# mcat-4cu-b-v2d.net
KiCad netlist of a schematic drawn in EAGLE
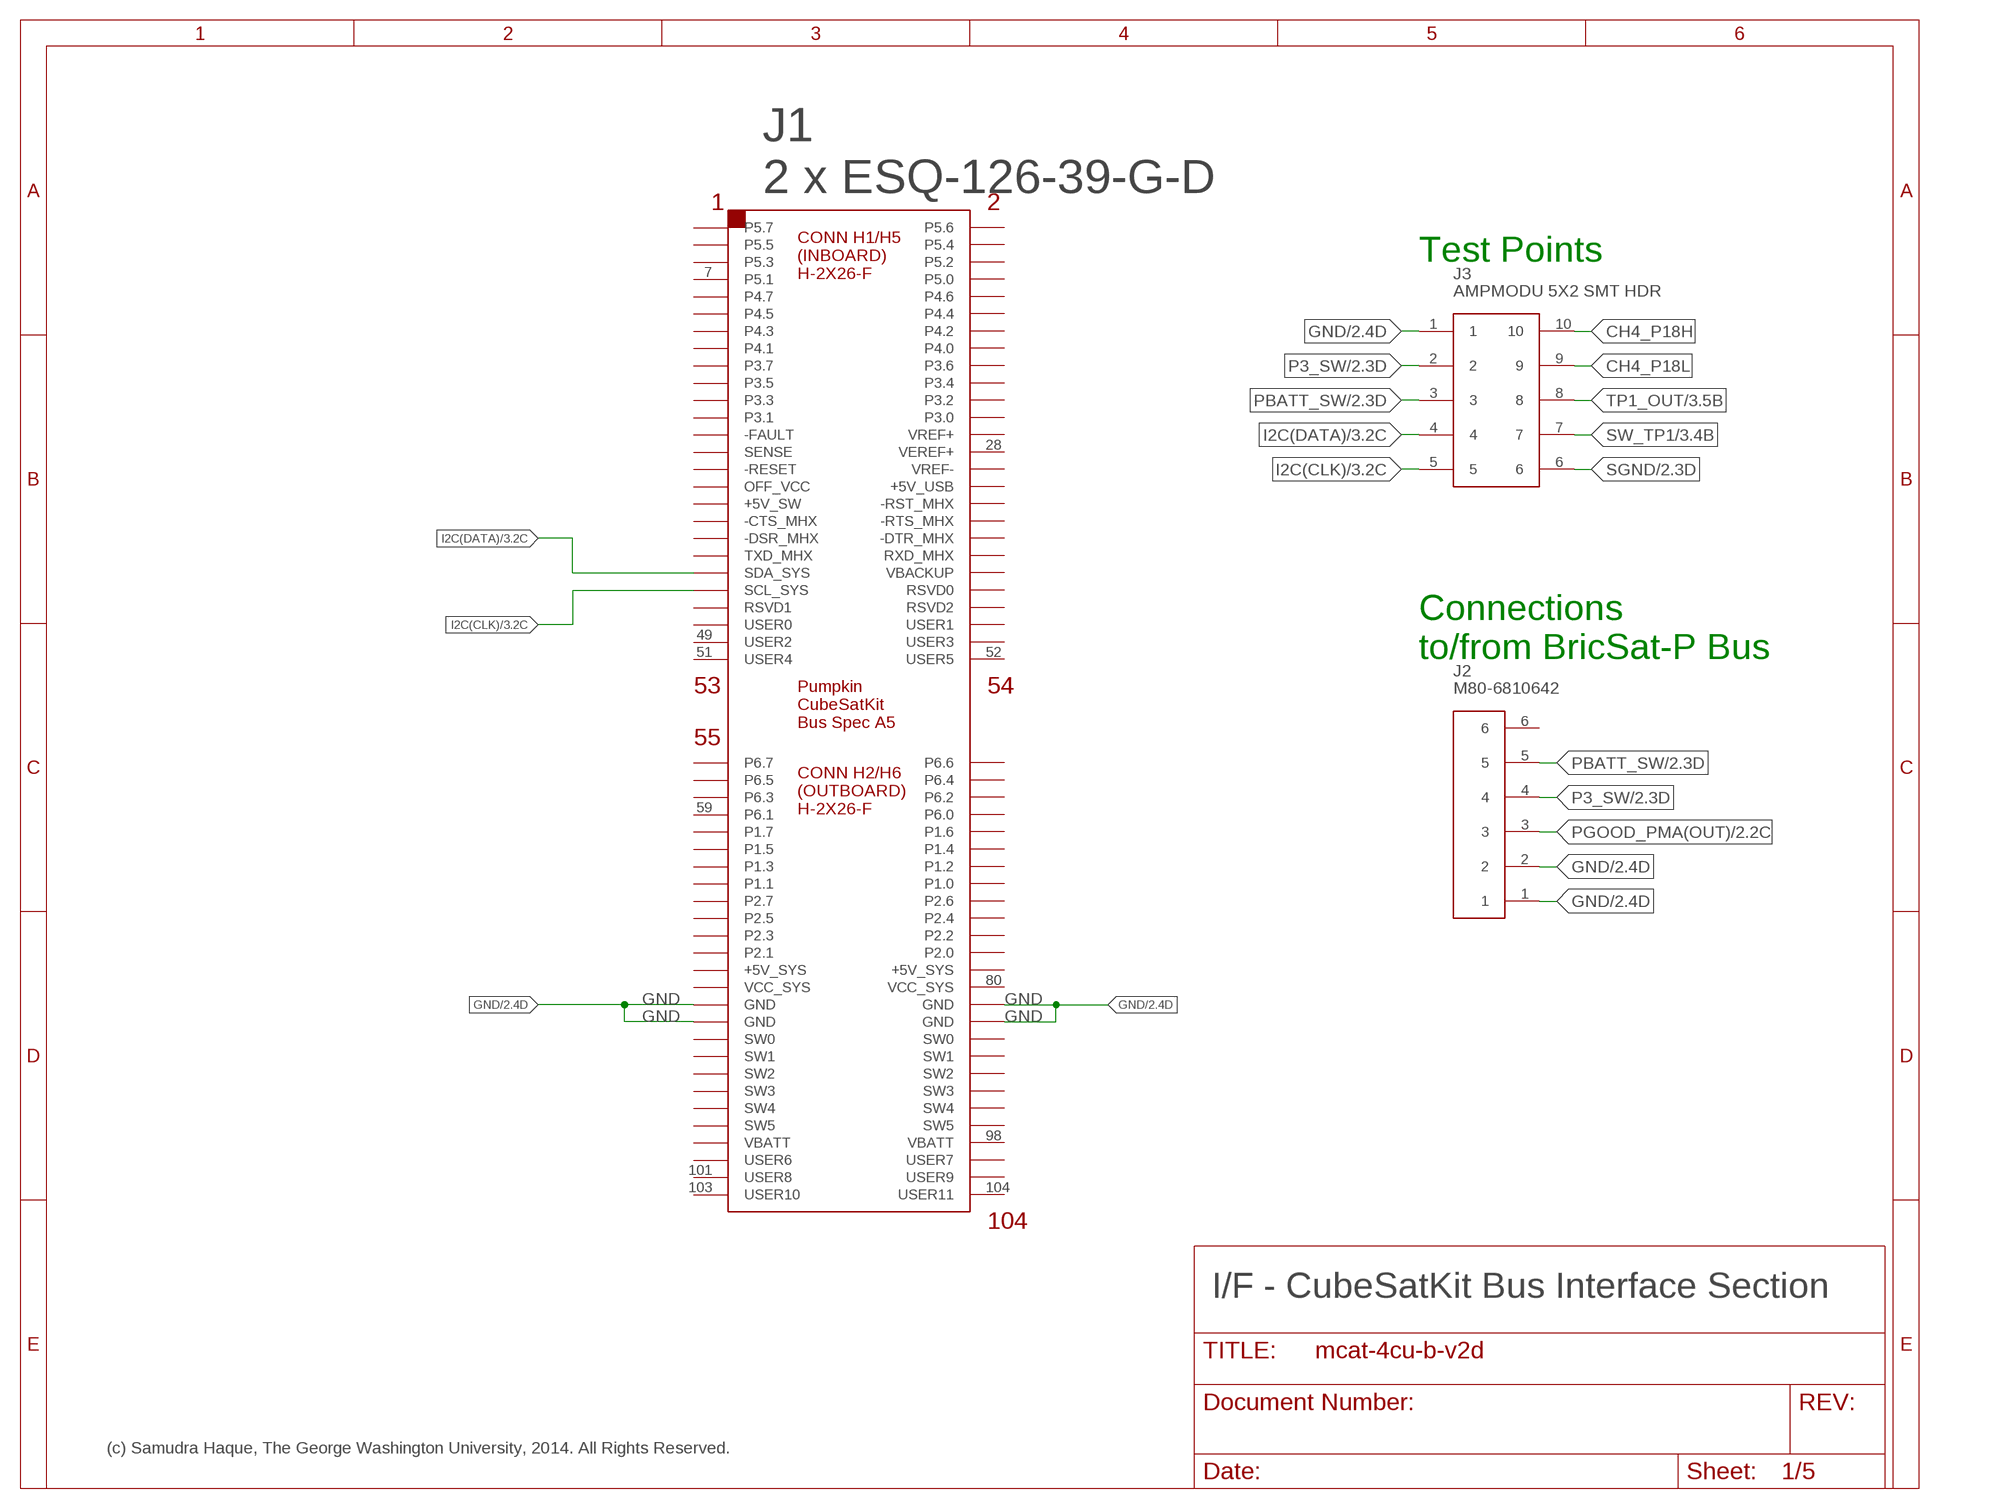
[diagram p0: schematic, sheet 1]
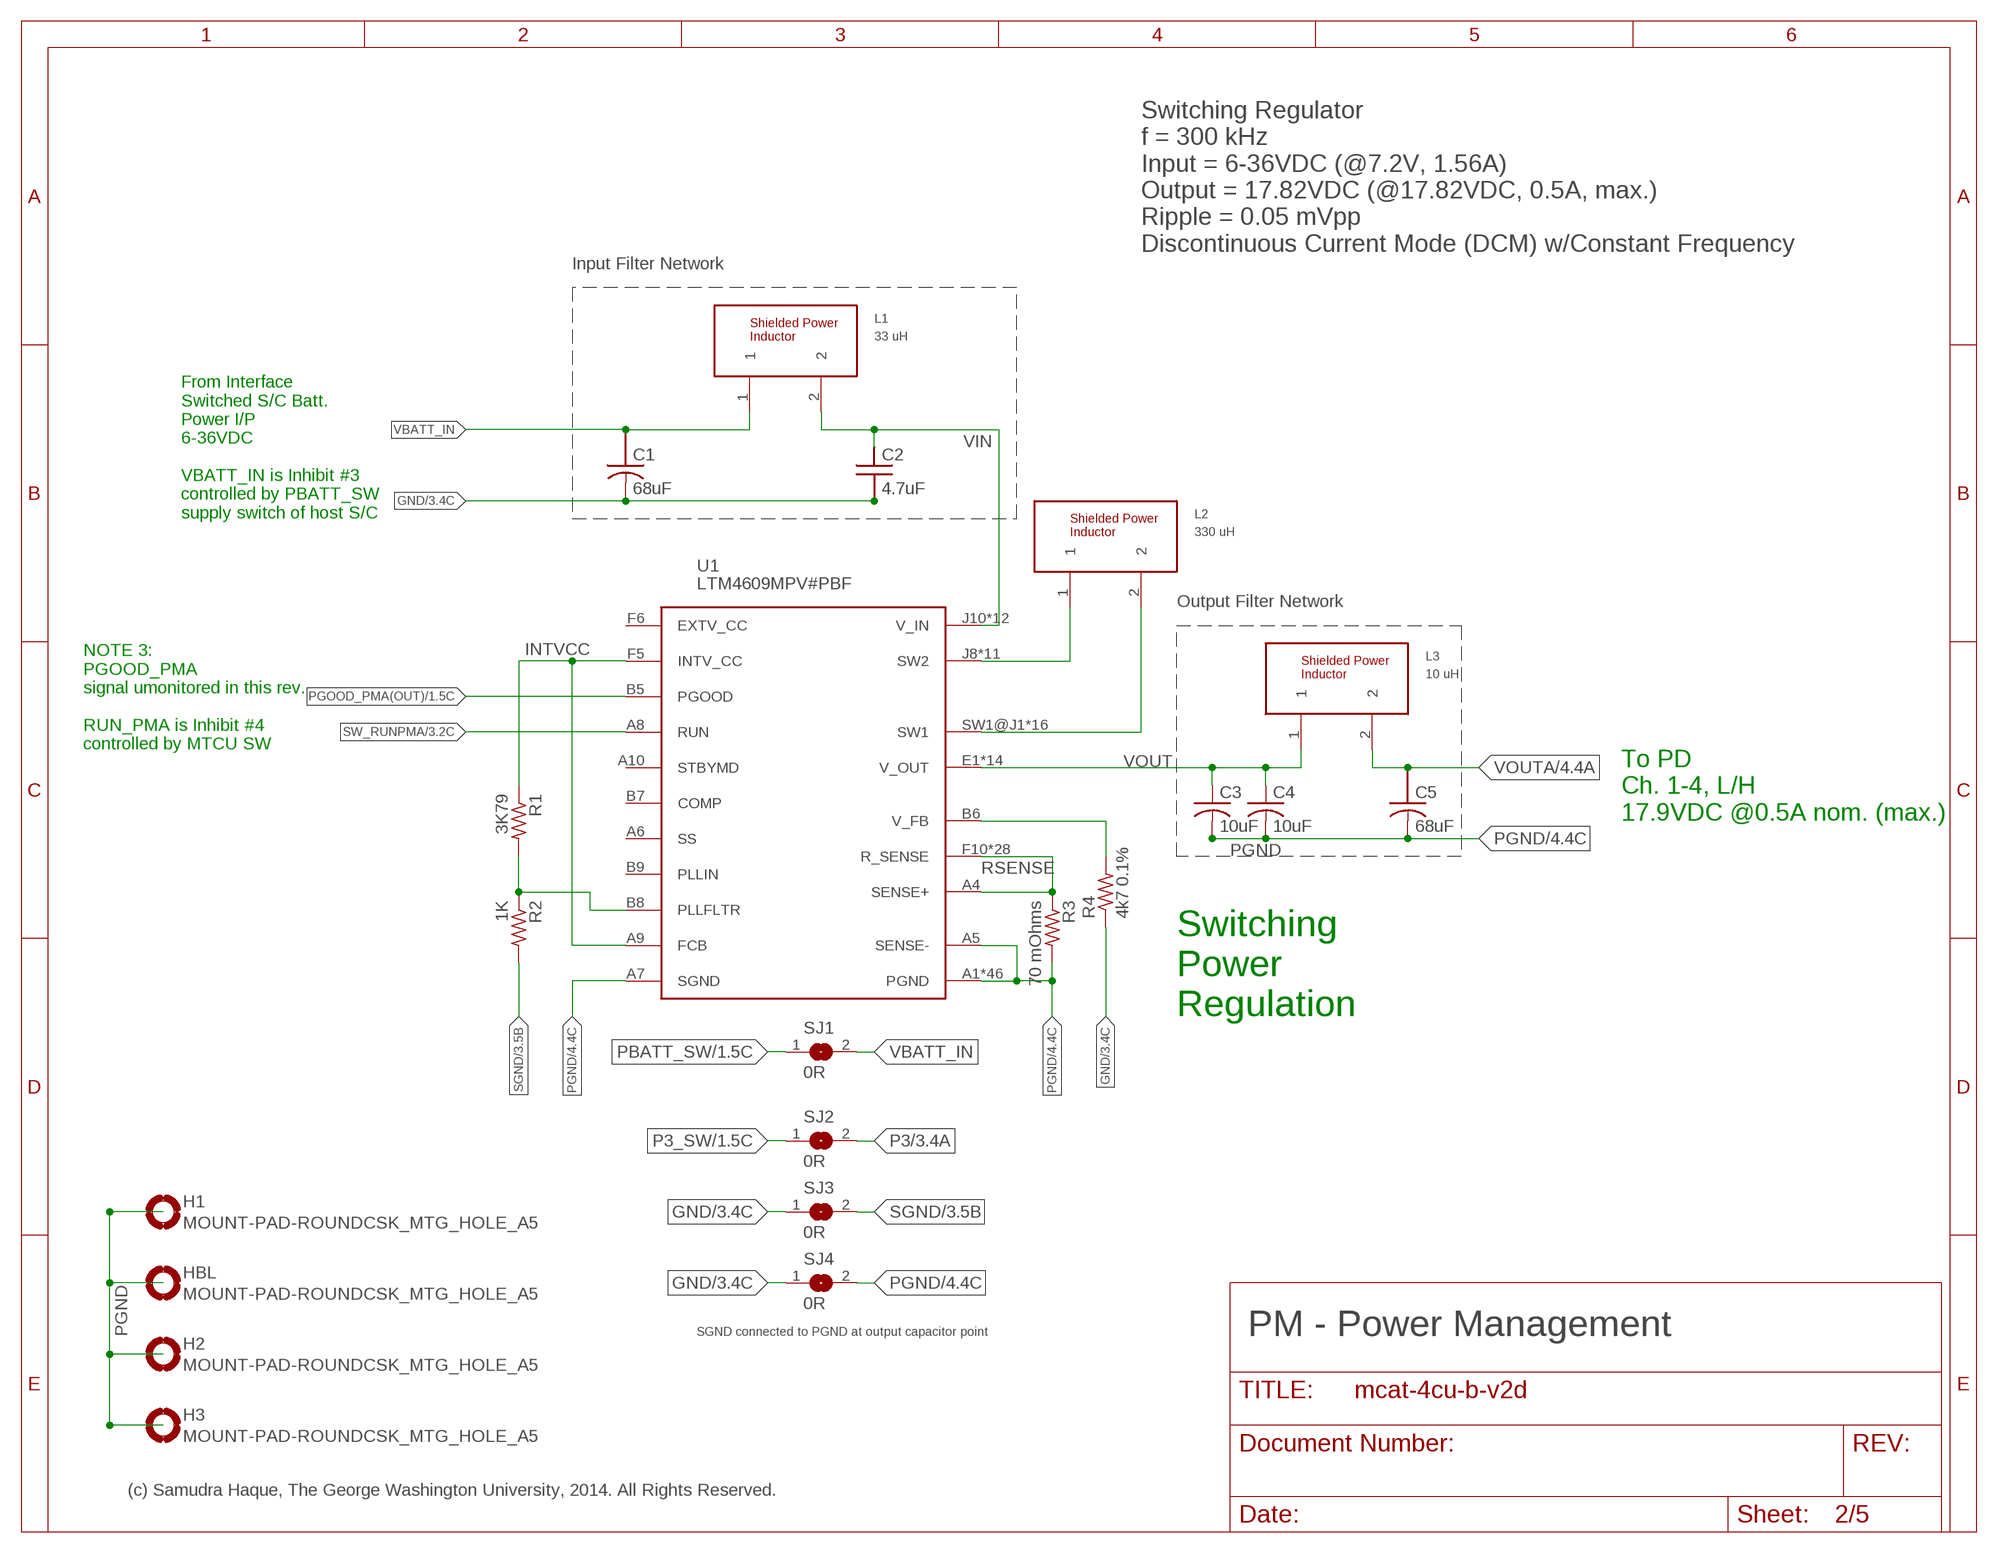
[diagram p1: schematic, sheet 2]
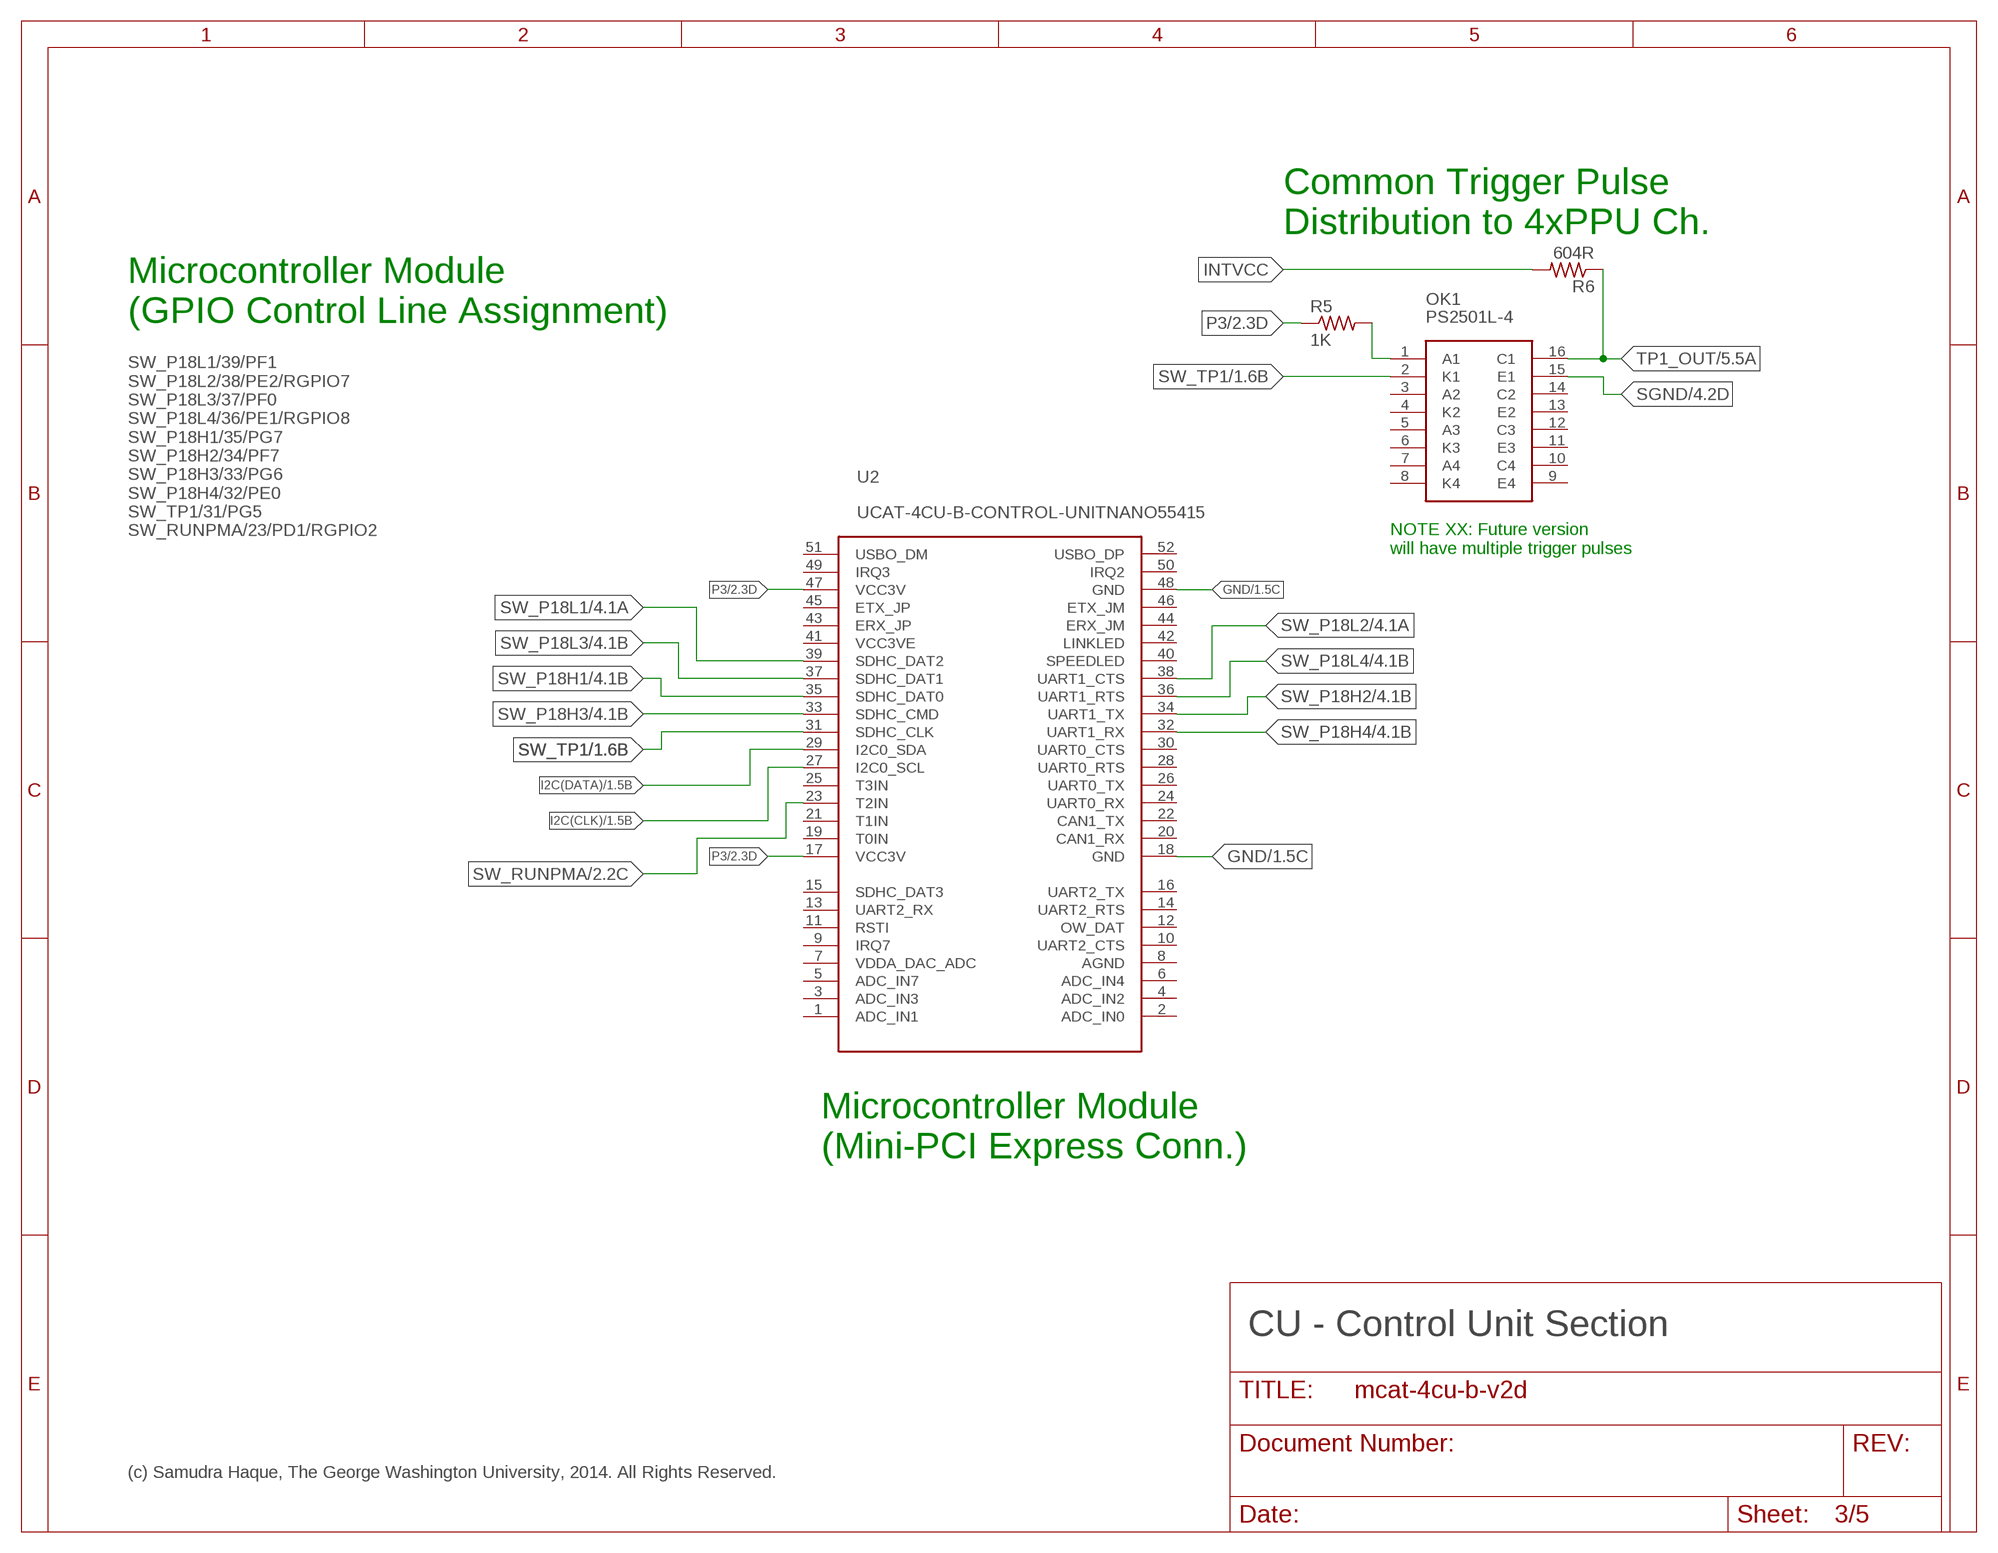
[diagram p2: schematic, sheet 3]
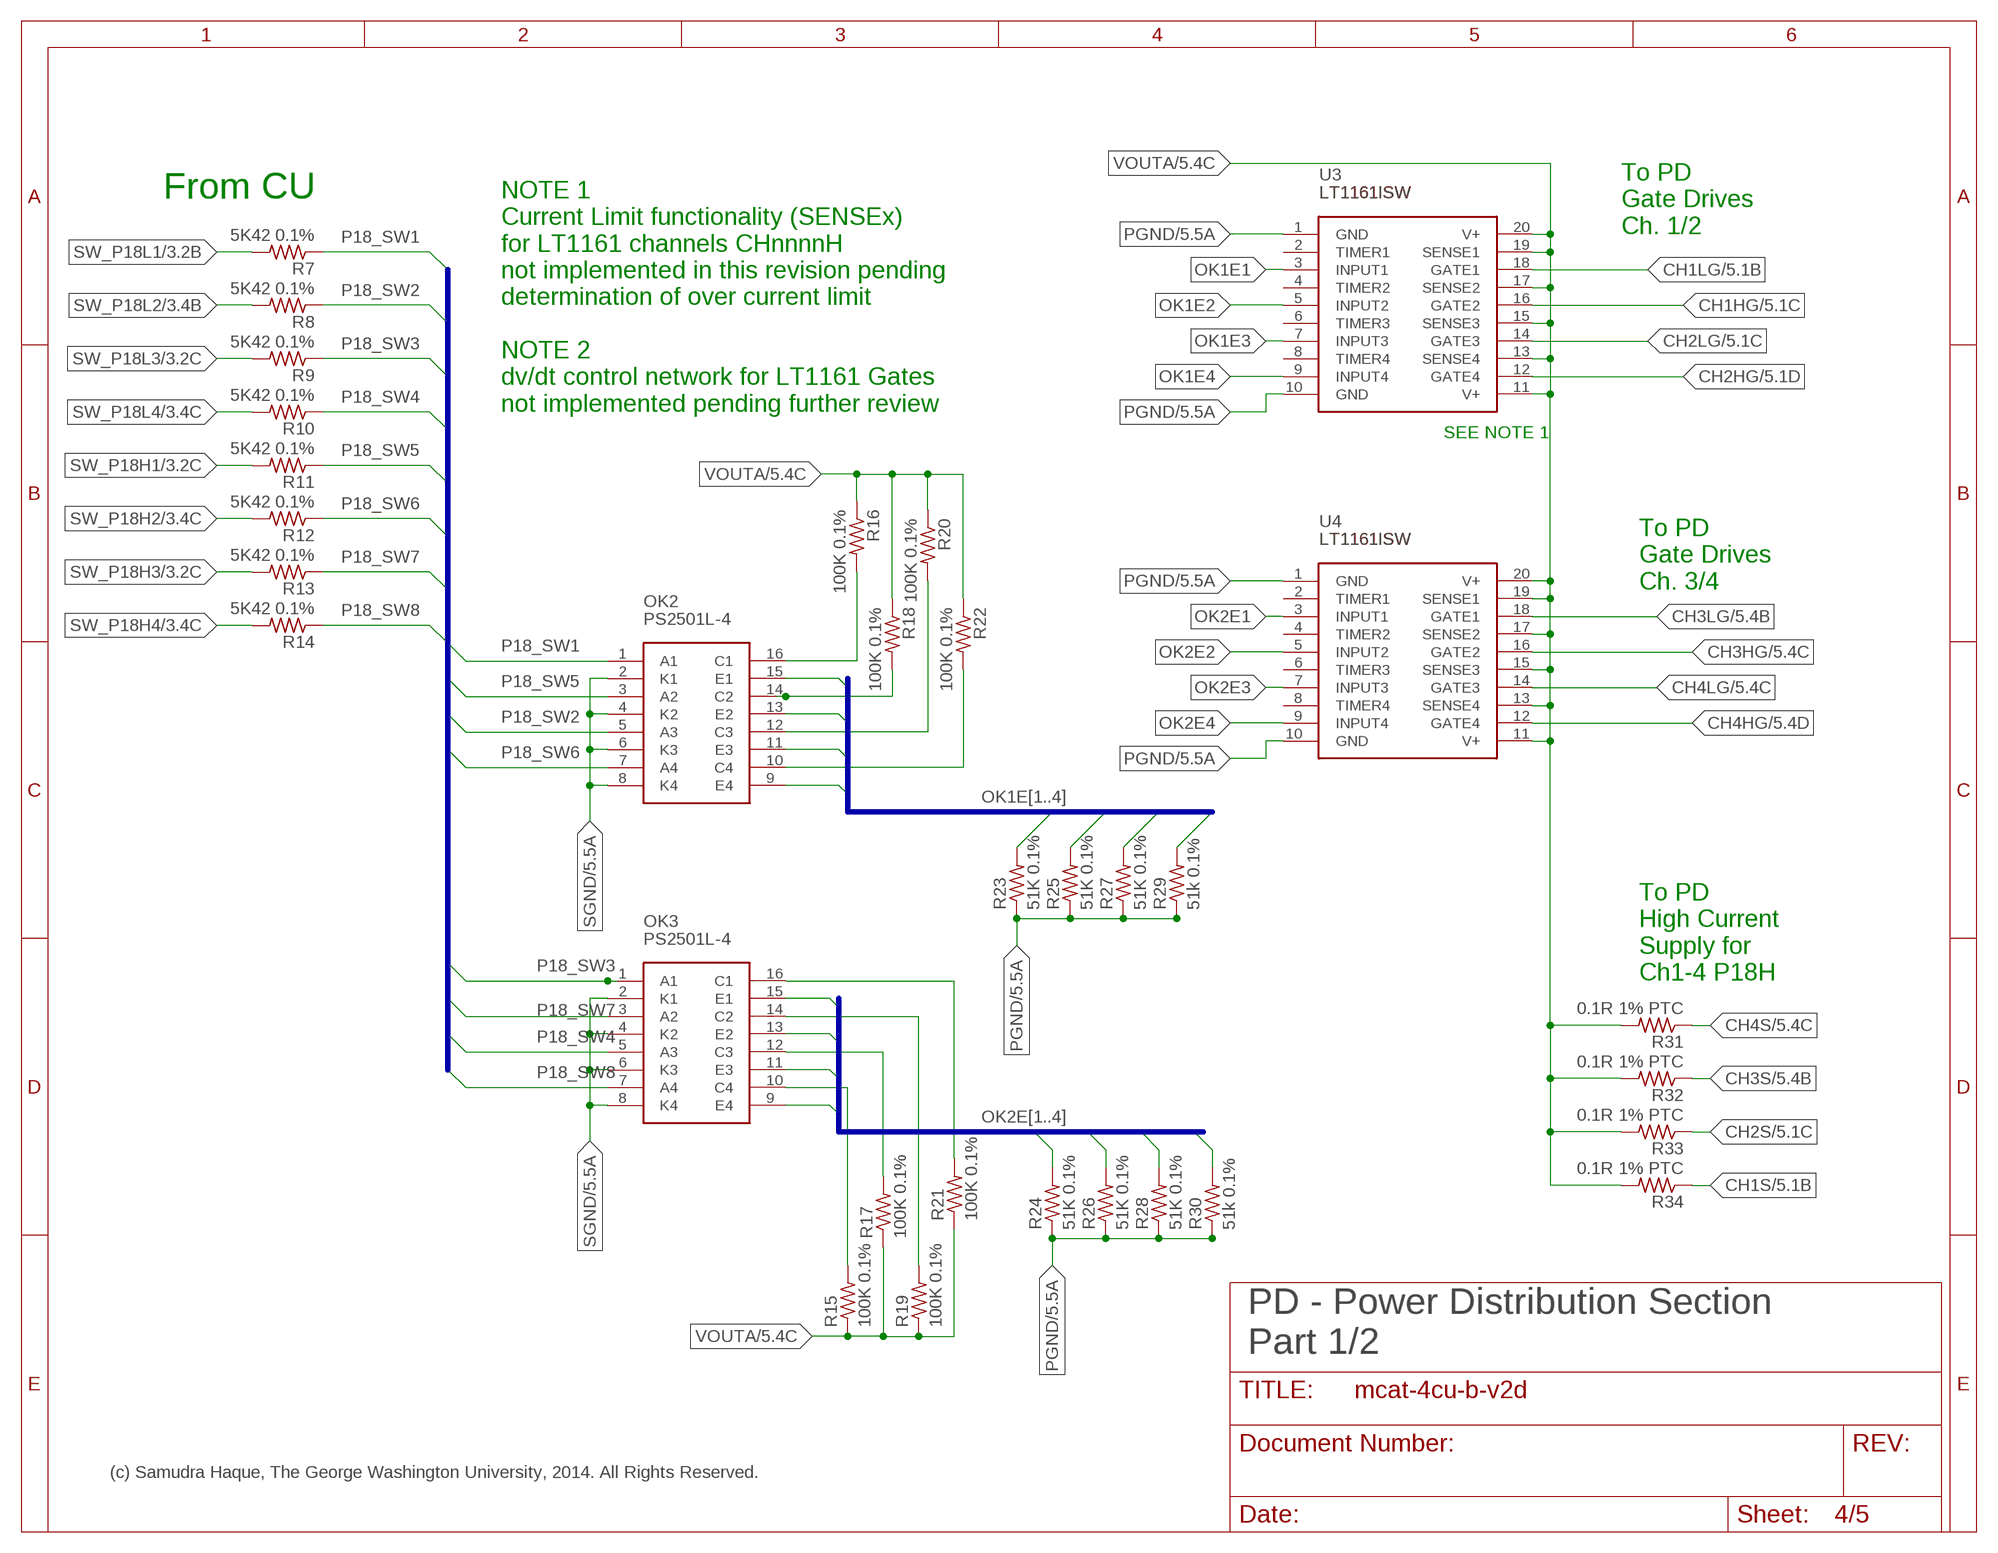
[diagram p3: schematic, sheet 4]
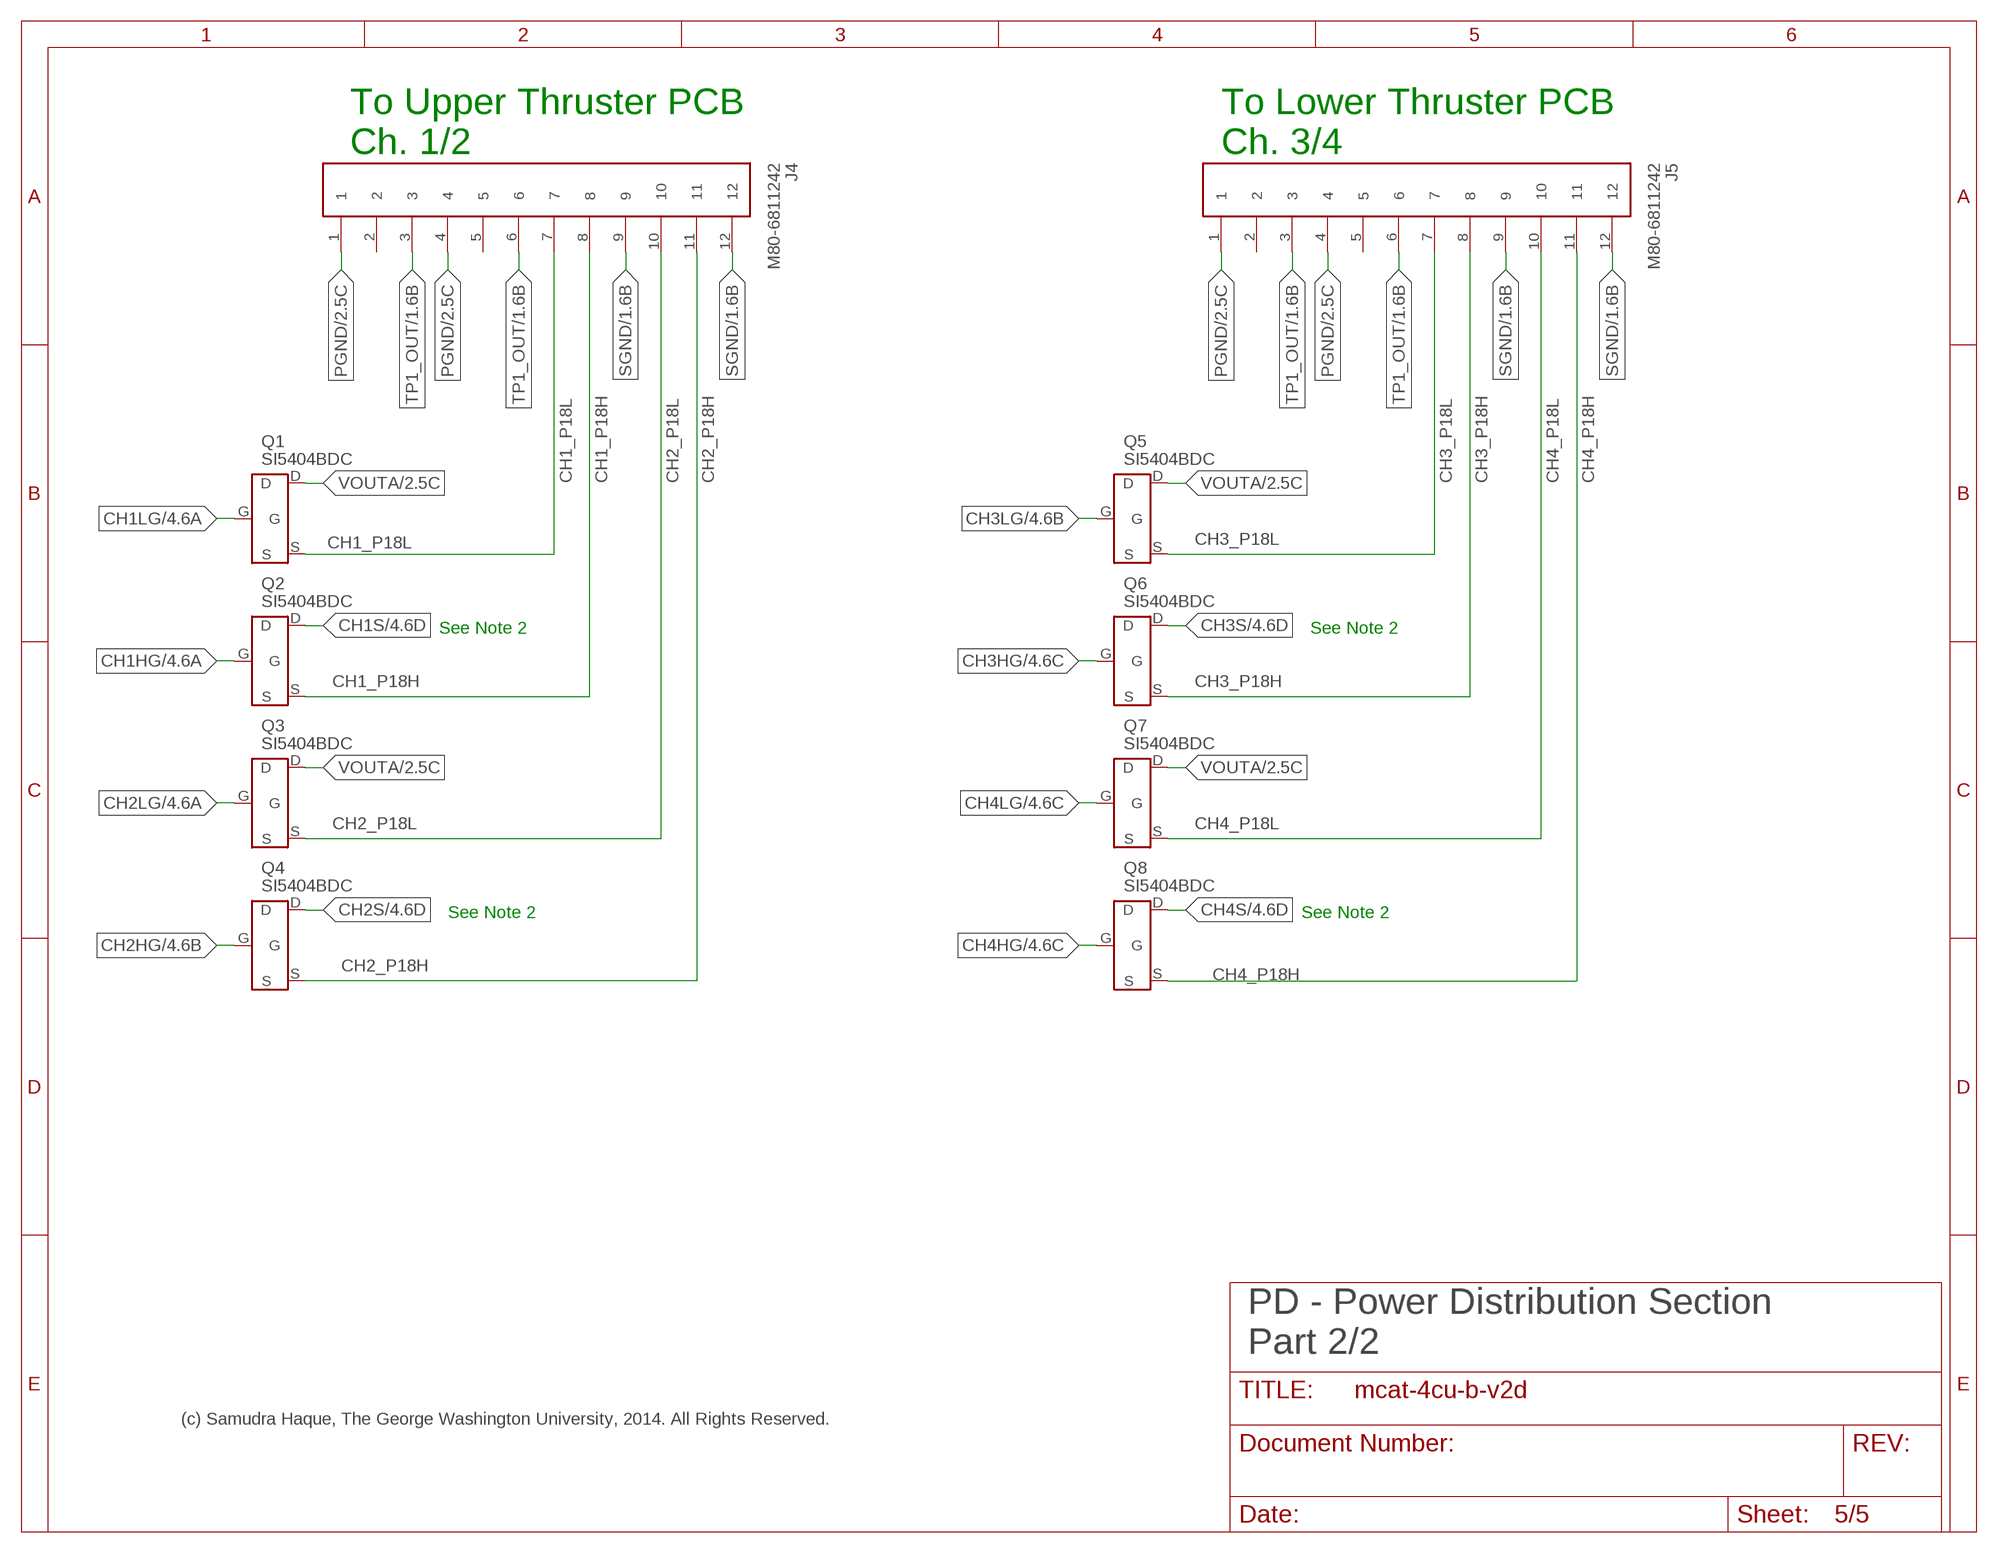
[diagram p4: schematic, sheet 5]

(export (version "E")
  (design (tool "Eeschema 10.0.6"))
  (components
    (comp (ref "OK1")
      (value "PS2501L-4")
      (footprint "eagle-import:PS2501L-4")
      (libsource (lib "eagle-import") (part "PS2501L-4"))
    )
    (comp (ref "R5")
      (value "1K")
      (footprint "eagle-import:R0805")
      (libsource (lib "eagle-import") (part "resistor_R-US_R0805"))
    )
    (comp (ref "R6")
      (value "604R")
      (footprint "eagle-import:R0805")
      (libsource (lib "eagle-import") (part "resistor_R-US_R0805"))
    )
    (comp (ref "U2")
      (value "UCAT-4CU-B-CONTROL-UNITNANO55415")
      (footprint "eagle-import:MOLEX-MINI-PCI-EXPRESS-8MM-52CKT")
      (libsource (lib "eagle-import") (part "UCAT-4CU-B-CONTROL-UNITNANO55415"))
    )
    (comp (ref "J4")
      (value "M80-6811242")
      (footprint "eagle-import:M80-68112")
      (libsource (lib "eagle-import") (part "M80-6811242"))
    )
    (comp (ref "J5")
      (value "M80-6811242")
      (footprint "eagle-import:M80-68112")
      (libsource (lib "eagle-import") (part "M80-6811242"))
    )
    (comp (ref "Q1")
      (value "SI5404BDC")
      (footprint "eagle-import:1206-8-CHIPFET")
      (libsource (lib "eagle-import") (part "SI5404BDC"))
    )
    (comp (ref "Q2")
      (value "SI5404BDC")
      (footprint "eagle-import:1206-8-CHIPFET")
      (libsource (lib "eagle-import") (part "SI5404BDC"))
    )
    (comp (ref "Q3")
      (value "SI5404BDC")
      (footprint "eagle-import:1206-8-CHIPFET")
      (libsource (lib "eagle-import") (part "SI5404BDC"))
    )
    (comp (ref "Q4")
      (value "SI5404BDC")
      (footprint "eagle-import:1206-8-CHIPFET")
      (libsource (lib "eagle-import") (part "SI5404BDC"))
    )
    (comp (ref "Q5")
      (value "SI5404BDC")
      (footprint "eagle-import:1206-8-CHIPFET")
      (libsource (lib "eagle-import") (part "SI5404BDC"))
    )
    (comp (ref "Q6")
      (value "SI5404BDC")
      (footprint "eagle-import:1206-8-CHIPFET")
      (libsource (lib "eagle-import") (part "SI5404BDC"))
    )
    (comp (ref "Q7")
      (value "SI5404BDC")
      (footprint "eagle-import:1206-8-CHIPFET")
      (libsource (lib "eagle-import") (part "SI5404BDC"))
    )
    (comp (ref "Q8")
      (value "SI5404BDC")
      (footprint "eagle-import:1206-8-CHIPFET")
      (libsource (lib "eagle-import") (part "SI5404BDC"))
    )
    (comp (ref "OK2")
      (value "PS2501L-4")
      (footprint "eagle-import:PS2501L-4")
      (libsource (lib "eagle-import") (part "PS2501L-4"))
    )
    (comp (ref "OK3")
      (value "PS2501L-4")
      (footprint "eagle-import:PS2501L-4")
      (libsource (lib "eagle-import") (part "PS2501L-4"))
    )
    (comp (ref "R7")
      (value "5K42 0.1%")
      (footprint "eagle-import:R1206")
      (libsource (lib "eagle-import") (part "resistor_R-US_R1206"))
    )
    (comp (ref "R8")
      (value "5K42 0.1%")
      (footprint "eagle-import:R1206")
      (libsource (lib "eagle-import") (part "resistor_R-US_R1206"))
    )
    (comp (ref "R9")
      (value "5K42 0.1%")
      (footprint "eagle-import:R1206")
      (libsource (lib "eagle-import") (part "resistor_R-US_R1206"))
    )
    (comp (ref "R10")
      (value "5K42 0.1%")
      (footprint "eagle-import:R1206")
      (libsource (lib "eagle-import") (part "resistor_R-US_R1206"))
    )
    (comp (ref "R11")
      (value "5K42 0.1%")
      (footprint "eagle-import:R1206")
      (libsource (lib "eagle-import") (part "resistor_R-US_R1206"))
    )
    (comp (ref "R12")
      (value "5K42 0.1%")
      (footprint "eagle-import:R1206")
      (libsource (lib "eagle-import") (part "resistor_R-US_R1206"))
    )
    (comp (ref "R13")
      (value "5K42 0.1%")
      (footprint "eagle-import:R1206")
      (libsource (lib "eagle-import") (part "resistor_R-US_R1206"))
    )
    (comp (ref "R14")
      (value "5K42 0.1%")
      (footprint "eagle-import:R1206")
      (libsource (lib "eagle-import") (part "resistor_R-US_R1206"))
    )
    (comp (ref "R15")
      (value "100K 0.1%")
      (footprint "eagle-import:R0402")
      (libsource (lib "eagle-import") (part "resistor_R-US_R0402"))
    )
    (comp (ref "R16")
      (value "100K 0.1%")
      (footprint "eagle-import:R0402")
      (libsource (lib "eagle-import") (part "resistor_R-US_R0402"))
    )
    (comp (ref "R17")
      (value "100K 0.1%")
      (footprint "eagle-import:R0402")
      (libsource (lib "eagle-import") (part "resistor_R-US_R0402"))
    )
    (comp (ref "R18")
      (value "100K 0.1%")
      (footprint "eagle-import:R0402")
      (libsource (lib "eagle-import") (part "resistor_R-US_R0402"))
    )
    (comp (ref "R19")
      (value "100K 0.1%")
      (footprint "eagle-import:R0402")
      (libsource (lib "eagle-import") (part "resistor_R-US_R0402"))
    )
    (comp (ref "R20")
      (value "100K 0.1%")
      (footprint "eagle-import:R0402")
      (libsource (lib "eagle-import") (part "resistor_R-US_R0402"))
    )
    (comp (ref "R21")
      (value "100K 0.1%")
      (footprint "eagle-import:R0402")
      (libsource (lib "eagle-import") (part "resistor_R-US_R0402"))
    )
    (comp (ref "R22")
      (value "100K 0.1%")
      (footprint "eagle-import:R0402")
      (libsource (lib "eagle-import") (part "resistor_R-US_R0402"))
    )
    (comp (ref "R23")
      (value "51K 0.1%")
      (footprint "eagle-import:R0603")
      (libsource (lib "eagle-import") (part "resistor_R-US_R0603"))
    )
    (comp (ref "R24")
      (value "51K 0.1%")
      (footprint "eagle-import:R0603")
      (libsource (lib "eagle-import") (part "resistor_R-US_R0603"))
    )
    (comp (ref "R25")
      (value "51K 0.1%")
      (footprint "eagle-import:R0603")
      (libsource (lib "eagle-import") (part "resistor_R-US_R0603"))
    )
    (comp (ref "R26")
      (value "51K 0.1%")
      (footprint "eagle-import:R0603")
      (libsource (lib "eagle-import") (part "resistor_R-US_R0603"))
    )
    (comp (ref "R27")
      (value "51K 0.1%")
      (footprint "eagle-import:R0603")
      (libsource (lib "eagle-import") (part "resistor_R-US_R0603"))
    )
    (comp (ref "R28")
      (value "51K 0.1%")
      (footprint "eagle-import:R0603")
      (libsource (lib "eagle-import") (part "resistor_R-US_R0603"))
    )
    (comp (ref "R29")
      (value "51k 0.1%")
      (footprint "eagle-import:R0603")
      (libsource (lib "eagle-import") (part "resistor_R-US_R0603"))
    )
    (comp (ref "R30")
      (value "51k 0.1%")
      (footprint "eagle-import:R0603")
      (libsource (lib "eagle-import") (part "resistor_R-US_R0603"))
    )
    (comp (ref "R31")
      (value "0.1R 1% PTC")
      (footprint "eagle-import:R0402")
      (libsource (lib "eagle-import") (part "R-US_R0402"))
    )
    (comp (ref "R32")
      (value "0.1R 1% PTC")
      (footprint "eagle-import:R0402")
      (libsource (lib "eagle-import") (part "R-US_R0402"))
    )
    (comp (ref "R33")
      (value "0.1R 1% PTC")
      (footprint "eagle-import:R0402")
      (libsource (lib "eagle-import") (part "R-US_R0402"))
    )
    (comp (ref "R34")
      (value "0.1R 1% PTC")
      (footprint "eagle-import:R0402")
      (libsource (lib "eagle-import") (part "R-US_R0402"))
    )
    (comp (ref "U3")
      (value "LT1161ISW")
      (footprint "eagle-import:20-LEAD-PLASTIC-SO")
      (libsource (lib "eagle-import") (part "LT1161ISW"))
    )
    (comp (ref "U4")
      (value "LT1161ISW")
      (footprint "eagle-import:20-LEAD-PLASTIC-SO")
      (libsource (lib "eagle-import") (part "LT1161ISW"))
    )
    (comp (ref "C1")
      (value "68uF")
      (footprint "eagle-import:OS-CON-SVPF-F12")
      (libsource (lib "eagle-import") (part "OSCON-50SVPF68M"))
    )
    (comp (ref "C2")
      (value "4.7uF")
      (footprint "eagle-import:MLCC-X7R-1210")
      (libsource (lib "eagle-import") (part "AVX-LD105C475KAB2A"))
    )
    (comp (ref "C3")
      (value "10uF")
      (footprint "eagle-import:C1210K")
      (libsource (lib "eagle-import") (part "C-USC1210K"))
    )
    (comp (ref "C4")
      (value "10uF")
      (footprint "eagle-import:C1210K")
      (libsource (lib "eagle-import") (part "C-USC1210K"))
    )
    (comp (ref "C5")
      (value "68uF")
      (footprint "eagle-import:OS-CON-SVPF-F12")
      (libsource (lib "eagle-import") (part "OSCON-50SVPF68M"))
    )
    (comp (ref "H1")
      (value "MOUNT-PAD-ROUNDCSK_MTG_HOLE_A5")
      (footprint "eagle-import:CSK_MOUNTING_HOLE")
      (libsource (lib "eagle-import") (part "MOUNT-PAD-ROUNDCSK_MTG_HOLE_A5"))
    )
    (comp (ref "H2")
      (value "MOUNT-PAD-ROUNDCSK_MTG_HOLE_A5")
      (footprint "eagle-import:CSK_MOUNTING_HOLE")
      (libsource (lib "eagle-import") (part "MOUNT-PAD-ROUNDCSK_MTG_HOLE_A5"))
    )
    (comp (ref "H3")
      (value "MOUNT-PAD-ROUNDCSK_MTG_HOLE_A5")
      (footprint "eagle-import:CSK_MOUNTING_HOLE")
      (libsource (lib "eagle-import") (part "MOUNT-PAD-ROUNDCSK_MTG_HOLE_A5"))
    )
    (comp (ref "HBL")
      (value "MOUNT-PAD-ROUNDCSK_MTG_HOLE_A5")
      (footprint "eagle-import:CSK_MOUNTING_HOLE")
      (libsource (lib "eagle-import") (part "MOUNT-PAD-ROUNDCSK_MTG_HOLE_A5"))
    )
    (comp (ref "L1")
      (value "33 uH")
      (footprint "eagle-import:MSS1048")
      (libsource (lib "eagle-import") (part "MSS1038-333ML_"))
    )
    (comp (ref "L2")
      (value "330 uH")
      (footprint "eagle-import:MSS1048")
      (libsource (lib "eagle-import") (part "MSS1048-334KL_"))
    )
    (comp (ref "L3")
      (value "10 uH")
      (footprint "eagle-import:SERIES-POWER-INDUCTORS")
      (fields (field (name "MF") "PANASONIC") (field (name "MPN") "ELL5PS100M"))
      (libsource (lib "eagle-import") (part "ELL-5PS100M"))
    )
    (comp (ref "R1")
      (value "3K79")
      (footprint "eagle-import:R0805")
      (libsource (lib "eagle-import") (part "R-US_R0805"))
    )
    (comp (ref "R2")
      (value "1K")
      (footprint "eagle-import:R0805")
      (libsource (lib "eagle-import") (part "R-US_R0805"))
    )
    (comp (ref "R3")
      (value "70 mOhms")
      (footprint "eagle-import:R1206")
      (libsource (lib "eagle-import") (part "resistor_R-US_R1206"))
    )
    (comp (ref "R4")
      (value "4k7 0.1%")
      (footprint "eagle-import:R0603")
      (libsource (lib "eagle-import") (part "resistor_R-US_R0603"))
    )
    (comp (ref "SJ1") (value "0R") (footprint "eagle-import:SJ") (libsource (lib "eagle-import") (part "SJ")))
    (comp (ref "SJ2") (value "0R") (footprint "eagle-import:SJ") (libsource (lib "eagle-import") (part "SJ")))
    (comp (ref "SJ3") (value "0R") (footprint "eagle-import:SJ") (libsource (lib "eagle-import") (part "SJ")))
    (comp (ref "SJ4") (value "0R") (footprint "eagle-import:SJ") (libsource (lib "eagle-import") (part "SJ")))
    (comp (ref "U1")
      (value "LTM4609MPV#PBF")
      (footprint "eagle-import:LGA-141-LTC-05-08-1840-B")
      (libsource (lib "eagle-import") (part "LTM4609MPV#PBFROHS/HITEMP"))
    )
    (comp (ref "J1")
      (value "2 x ESQ-126-39-G-D")
      (footprint "eagle-import:CSK-BUS-PKG")
      (libsource (lib "eagle-import") (part "CSK-BUS-CONN2X2X26"))
    )
    (comp (ref "J2")
      (value "M80-6810642")
      (footprint "eagle-import:M80-68106")
      (libsource (lib "eagle-import") (part "M80-6810642"))
    )
    (comp (ref "J3")
      (value "AMPMODU 5X2 SMT HDR")
      (footprint "eagle-import:AMPMODU-SMT-PIN-HEADER-5X2")
      (libsource (lib "eagle-import") (part "AMPMODU-5-146131-X(5X2)"))
    )
  )
  (nets
    (net (code "3") (name "CH1HG") (class "Default")
      (node (ref "Q2") (pin "G") (pinfunction "G_G") (pintype "bidirectional"))
      (node (ref "U3") (pin "16") (pinfunction "GATE2_16") (pintype "bidirectional"))
    )
    (net (code "4") (name "CH1LG") (class "Default")
      (node (ref "Q1") (pin "G") (pinfunction "G_G") (pintype "bidirectional"))
      (node (ref "U3") (pin "18") (pinfunction "GATE1_18") (pintype "bidirectional"))
    )
    (net (code "5") (name "CH1S") (class "Default")
      (node (ref "Q2") (pin "D") (pinfunction "D_D") (pintype "bidirectional"))
      (node (ref "R34") (pin "1") (pinfunction "1_1") (pintype "passive"))
    )
    (net (code "6") (name "CH1_P18H") (class "Default")
      (node (ref "J4") (pin "8") (pinfunction "8_8") (pintype "bidirectional"))
      (node (ref "Q2") (pin "S") (pinfunction "S_S") (pintype "bidirectional"))
    )
    (net (code "7") (name "CH1_P18L") (class "Default")
      (node (ref "J4") (pin "7") (pinfunction "7_7") (pintype "bidirectional"))
      (node (ref "Q1") (pin "S") (pinfunction "S_S") (pintype "bidirectional"))
    )
    (net (code "8") (name "CH2HG") (class "Default")
      (node (ref "Q4") (pin "G") (pinfunction "G_G") (pintype "bidirectional"))
      (node (ref "U3") (pin "12") (pinfunction "GATE4_12") (pintype "bidirectional"))
    )
    (net (code "9") (name "CH2LG") (class "Default")
      (node (ref "Q3") (pin "G") (pinfunction "G_G") (pintype "bidirectional"))
      (node (ref "U3") (pin "14") (pinfunction "GATE3_14") (pintype "bidirectional"))
    )
    (net (code "10") (name "CH2S") (class "Default")
      (node (ref "Q4") (pin "D") (pinfunction "D_D") (pintype "bidirectional"))
      (node (ref "R33") (pin "1") (pinfunction "1_1") (pintype "passive"))
    )
    (net (code "11") (name "CH2_P18H") (class "Default")
      (node (ref "J4") (pin "11") (pinfunction "11_11") (pintype "bidirectional"))
      (node (ref "Q4") (pin "S") (pinfunction "S_S") (pintype "bidirectional"))
    )
    (net (code "12") (name "CH2_P18L") (class "Default")
      (node (ref "J4") (pin "10") (pinfunction "10_10") (pintype "bidirectional"))
      (node (ref "Q3") (pin "S") (pinfunction "S_S") (pintype "bidirectional"))
    )
    (net (code "13") (name "CH3HG") (class "Default")
      (node (ref "Q6") (pin "G") (pinfunction "G_G") (pintype "bidirectional"))
      (node (ref "U4") (pin "16") (pinfunction "GATE2_16") (pintype "bidirectional"))
    )
    (net (code "14") (name "CH3LG") (class "Default")
      (node (ref "Q5") (pin "G") (pinfunction "G_G") (pintype "bidirectional"))
      (node (ref "U4") (pin "18") (pinfunction "GATE1_18") (pintype "bidirectional"))
    )
    (net (code "15") (name "CH3S") (class "Default")
      (node (ref "Q6") (pin "D") (pinfunction "D_D") (pintype "bidirectional"))
      (node (ref "R32") (pin "1") (pinfunction "1_1") (pintype "passive"))
    )
    (net (code "16") (name "CH3_P18H") (class "Default")
      (node (ref "J5") (pin "8") (pinfunction "8_8") (pintype "bidirectional"))
      (node (ref "Q6") (pin "S") (pinfunction "S_S") (pintype "bidirectional"))
    )
    (net (code "17") (name "CH3_P18L") (class "Default")
      (node (ref "J5") (pin "7") (pinfunction "7_7") (pintype "bidirectional"))
      (node (ref "Q5") (pin "S") (pinfunction "S_S") (pintype "bidirectional"))
    )
    (net (code "18") (name "CH4HG") (class "Default")
      (node (ref "Q8") (pin "G") (pinfunction "G_G") (pintype "bidirectional"))
      (node (ref "U4") (pin "12") (pinfunction "GATE4_12") (pintype "bidirectional"))
    )
    (net (code "19") (name "CH4LG") (class "Default")
      (node (ref "Q7") (pin "G") (pinfunction "G_G") (pintype "bidirectional"))
      (node (ref "U4") (pin "14") (pinfunction "GATE3_14") (pintype "bidirectional"))
    )
    (net (code "20") (name "CH4S") (class "Default")
      (node (ref "Q8") (pin "D") (pinfunction "D_D") (pintype "bidirectional"))
      (node (ref "R31") (pin "1") (pinfunction "1_1") (pintype "passive"))
    )
    (net (code "21") (name "CH4_P18H") (class "Default")
      (node (ref "J3") (pin "10") (pinfunction "10_10") (pintype "bidirectional"))
      (node (ref "J5") (pin "11") (pinfunction "11_11") (pintype "bidirectional"))
      (node (ref "Q8") (pin "S") (pinfunction "S_S") (pintype "bidirectional"))
    )
    (net (code "22") (name "CH4_P18L") (class "Default")
      (node (ref "J3") (pin "9") (pinfunction "9_9") (pintype "bidirectional"))
      (node (ref "J5") (pin "10") (pinfunction "10_10") (pintype "bidirectional"))
      (node (ref "Q7") (pin "S") (pinfunction "S_S") (pintype "bidirectional"))
    )
    (net (code "23") (name "GND") (class "Default")
      (node (ref "C1") (pin "K1") (pinfunction "K_K1") (pintype "passive"))
      (node (ref "C2") (pin "2") (pinfunction "2_2") (pintype "passive"))
      (node (ref "J1") (pin "81") (pinfunction "GND_81") (pintype "bidirectional"))
      (node (ref "J1") (pin "82") (pinfunction "GND_82") (pintype "bidirectional"))
      (node (ref "J1") (pin "83") (pinfunction "GND_83") (pintype "bidirectional"))
      (node (ref "J1") (pin "84") (pinfunction "GND_84") (pintype "bidirectional"))
      (node (ref "J2") (pin "1") (pinfunction "1_1") (pintype "bidirectional"))
      (node (ref "J2") (pin "2") (pinfunction "2_2") (pintype "bidirectional"))
      (node (ref "J3") (pin "1") (pinfunction "1_1") (pintype "bidirectional"))
      (node (ref "R4") (pin "1") (pinfunction "1_1") (pintype "passive"))
      (node (ref "SJ3") (pin "1") (pinfunction "1_1") (pintype "passive"))
      (node (ref "SJ4") (pin "1") (pinfunction "1_1") (pintype "passive"))
      (node (ref "U2") (pin "18") (pinfunction "GND_18") (pintype "bidirectional"))
      (node (ref "U2") (pin "48") (pinfunction "GND_48") (pintype "bidirectional"))
    )
    (net (code "24") (name "I2C(CLK)") (class "Default")
      (node (ref "J1") (pin "43") (pinfunction "SCL_SYS_43") (pintype "bidirectional"))
      (node (ref "J3") (pin "5") (pinfunction "5_5") (pintype "bidirectional"))
      (node (ref "U2") (pin "27") (pinfunction "I2C0_SCL_27") (pintype "bidirectional"))
    )
    (net (code "25") (name "I2C(DATA)") (class "Default")
      (node (ref "J1") (pin "41") (pinfunction "SDA_SYS_41") (pintype "bidirectional"))
      (node (ref "J3") (pin "4") (pinfunction "4_4") (pintype "bidirectional"))
      (node (ref "U2") (pin "29") (pinfunction "I2C0_SDA_29") (pintype "bidirectional"))
    )
    (net (code "26") (name "INTVCC") (class "Default")
      (node (ref "R1") (pin "1") (pinfunction "1_1") (pintype "passive"))
      (node (ref "R6") (pin "2") (pinfunction "2_2") (pintype "passive"))
      (node (ref "U1") (pin "A9") (pinfunction "FCB_A9") (pintype "bidirectional"))
      (node (ref "U1") (pin "F5") (pinfunction "INTV_CC_F5") (pintype "bidirectional"))
    )
    (net (code "27") (name "Net-(L2-Pad1)") (class "Default")
      (node (ref "L2") (pin "1") (pinfunction "1_1") (pintype "bidirectional"))
      (node (ref "U1") (pin "J8") (pinfunction "SW2_J8") (pintype "bidirectional"))
      (node (ref "U1") (pin "J9") (pinfunction "SW2_J9") (pintype "bidirectional"))
      (node (ref "U1") (pin "K7") (pinfunction "SW2_K7") (pintype "bidirectional"))
      (node (ref "U1") (pin "K8") (pinfunction "SW2_K8") (pintype "bidirectional"))
      (node (ref "U1") (pin "K9") (pinfunction "SW2_K9") (pintype "bidirectional"))
      (node (ref "U1") (pin "L7") (pinfunction "SW2_L7") (pintype "bidirectional"))
      (node (ref "U1") (pin "L8") (pinfunction "SW2_L8") (pintype "bidirectional"))
      (node (ref "U1") (pin "L9") (pinfunction "SW2_L9") (pintype "bidirectional"))
      (node (ref "U1") (pin "M7") (pinfunction "SW2_M7") (pintype "bidirectional"))
      (node (ref "U1") (pin "M8") (pinfunction "SW2_M8") (pintype "bidirectional"))
      (node (ref "U1") (pin "M9") (pinfunction "SW2_M9") (pintype "bidirectional"))
    )
    (net (code "28") (name "Net-(L2-Pad2)") (class "Default")
      (node (ref "L2") (pin "2") (pinfunction "2_2") (pintype "bidirectional"))
      (node (ref "U1") (pin "SW1@J1") (pinfunction "SW1_SW1@J1") (pintype "bidirectional"))
      (node (ref "U1") (pin "SW1@J2") (pinfunction "SW1_SW1@J2") (pintype "bidirectional"))
      (node (ref "U1") (pin "SW1@J3") (pinfunction "SW1_SW1@J3") (pintype "bidirectional"))
      (node (ref "U1") (pin "SW1@J4") (pinfunction "SW1_SW1@J4") (pintype "bidirectional"))
      (node (ref "U1") (pin "SW1@K1") (pinfunction "SW1_SW1@K1") (pintype "bidirectional"))
      (node (ref "U1") (pin "SW1@K2") (pinfunction "SW1_SW1@K2") (pintype "bidirectional"))
      (node (ref "U1") (pin "SW1@K3") (pinfunction "SW1_SW1@K3") (pintype "bidirectional"))
      (node (ref "U1") (pin "SW1@K4") (pinfunction "SW1_SW1@K4") (pintype "bidirectional"))
      (node (ref "U1") (pin "SW1@L1") (pinfunction "SW1_SW1@L1") (pintype "bidirectional"))
      (node (ref "U1") (pin "SW1@L2") (pinfunction "SW1_SW1@L2") (pintype "bidirectional"))
      (node (ref "U1") (pin "SW1@L3") (pinfunction "SW1_SW1@L3") (pintype "bidirectional"))
      (node (ref "U1") (pin "SW1@L4") (pinfunction "SW1_SW1@L4") (pintype "bidirectional"))
      (node (ref "U1") (pin "SW1@M1") (pinfunction "SW1_SW1@M1") (pintype "bidirectional"))
      (node (ref "U1") (pin "SW1@M2") (pinfunction "SW1_SW1@M2") (pintype "bidirectional"))
      (node (ref "U1") (pin "SW1@M3") (pinfunction "SW1_SW1@M3") (pintype "bidirectional"))
      (node (ref "U1") (pin "SW1@M4") (pinfunction "SW1_SW1@M4") (pintype "bidirectional"))
    )
    (net (code "29") (name "Net-(OK1-A1)") (class "Default")
      (node (ref "OK1") (pin "1") (pinfunction "A1_1") (pintype "bidirectional"))
      (node (ref "R5") (pin "2") (pinfunction "2_2") (pintype "passive"))
    )
    (net (code "30") (name "Net-(OK2-C1)") (class "Default")
      (node (ref "OK2") (pin "16") (pinfunction "C1_16") (pintype "bidirectional"))
      (node (ref "R16") (pin "2") (pinfunction "2_2") (pintype "passive"))
    )
    (net (code "31") (name "Net-(OK2-C2)") (class "Default")
      (node (ref "OK2") (pin "14") (pinfunction "C2_14") (pintype "bidirectional"))
      (node (ref "R18") (pin "2") (pinfunction "2_2") (pintype "passive"))
    )
    (net (code "32") (name "Net-(OK2-C3)") (class "Default")
      (node (ref "OK2") (pin "12") (pinfunction "C3_12") (pintype "bidirectional"))
      (node (ref "R20") (pin "2") (pinfunction "2_2") (pintype "passive"))
    )
    (net (code "33") (name "Net-(OK2-C4)") (class "Default")
      (node (ref "OK2") (pin "10") (pinfunction "C4_10") (pintype "bidirectional"))
      (node (ref "R22") (pin "2") (pinfunction "2_2") (pintype "passive"))
    )
    (net (code "34") (name "Net-(OK3-C1)") (class "Default")
      (node (ref "OK3") (pin "16") (pinfunction "C1_16") (pintype "bidirectional"))
      (node (ref "R21") (pin "2") (pinfunction "2_2") (pintype "passive"))
    )
    (net (code "35") (name "Net-(OK3-C2)") (class "Default")
      (node (ref "OK3") (pin "14") (pinfunction "C2_14") (pintype "bidirectional"))
      (node (ref "R19") (pin "2") (pinfunction "2_2") (pintype "passive"))
    )
    (net (code "36") (name "Net-(OK3-C3)") (class "Default")
      (node (ref "OK3") (pin "12") (pinfunction "C3_12") (pintype "bidirectional"))
      (node (ref "R17") (pin "2") (pinfunction "2_2") (pintype "passive"))
    )
    (net (code "37") (name "Net-(OK3-C4)") (class "Default")
      (node (ref "OK3") (pin "10") (pinfunction "C4_10") (pintype "bidirectional"))
      (node (ref "R15") (pin "2") (pinfunction "2_2") (pintype "passive"))
    )
    (net (code "38") (name "Net-(U1-PLLFLTR)") (class "Default")
      (node (ref "R1") (pin "2") (pinfunction "2_2") (pintype "passive"))
      (node (ref "R2") (pin "1") (pinfunction "1_1") (pintype "passive"))
      (node (ref "U1") (pin "B8") (pinfunction "PLLFLTR_B8") (pintype "bidirectional"))
    )
    (net (code "39") (name "Net-(U1-V_FB)") (class "Default")
      (node (ref "R4") (pin "2") (pinfunction "2_2") (pintype "passive"))
      (node (ref "U1") (pin "B6") (pinfunction "V_FB_B6") (pintype "bidirectional"))
    )
    (net (code "40") (name "OK1E1") (class "Default")
      (node (ref "OK2") (pin "15") (pinfunction "E1_15") (pintype "bidirectional"))
      (node (ref "R23") (pin "2") (pinfunction "2_2") (pintype "passive"))
      (node (ref "U3") (pin "3") (pinfunction "INPUT1_3") (pintype "bidirectional"))
    )
    (net (code "41") (name "OK1E2") (class "Default")
      (node (ref "OK2") (pin "13") (pinfunction "E2_13") (pintype "bidirectional"))
      (node (ref "R25") (pin "2") (pinfunction "2_2") (pintype "passive"))
      (node (ref "U3") (pin "5") (pinfunction "INPUT2_5") (pintype "bidirectional"))
    )
    (net (code "42") (name "OK1E3") (class "Default")
      (node (ref "OK2") (pin "11") (pinfunction "E3_11") (pintype "bidirectional"))
      (node (ref "R27") (pin "2") (pinfunction "2_2") (pintype "passive"))
      (node (ref "U3") (pin "7") (pinfunction "INPUT3_7") (pintype "bidirectional"))
    )
    (net (code "43") (name "OK1E4") (class "Default")
      (node (ref "OK2") (pin "9") (pinfunction "E4_9") (pintype "bidirectional"))
      (node (ref "R29") (pin "2") (pinfunction "2_2") (pintype "passive"))
      (node (ref "U3") (pin "9") (pinfunction "INPUT4_9") (pintype "bidirectional"))
    )
    (net (code "44") (name "OK2E1") (class "Default")
      (node (ref "OK3") (pin "15") (pinfunction "E1_15") (pintype "bidirectional"))
      (node (ref "R24") (pin "2") (pinfunction "2_2") (pintype "passive"))
      (node (ref "U4") (pin "3") (pinfunction "INPUT1_3") (pintype "bidirectional"))
    )
    (net (code "45") (name "OK2E2") (class "Default")
      (node (ref "OK3") (pin "13") (pinfunction "E2_13") (pintype "bidirectional"))
      (node (ref "R26") (pin "2") (pinfunction "2_2") (pintype "passive"))
      (node (ref "U4") (pin "5") (pinfunction "INPUT2_5") (pintype "bidirectional"))
    )
    (net (code "46") (name "OK2E3") (class "Default")
      (node (ref "OK3") (pin "11") (pinfunction "E3_11") (pintype "bidirectional"))
      (node (ref "R28") (pin "2") (pinfunction "2_2") (pintype "passive"))
      (node (ref "U4") (pin "7") (pinfunction "INPUT3_7") (pintype "bidirectional"))
    )
    (net (code "47") (name "OK2E4") (class "Default")
      (node (ref "OK3") (pin "9") (pinfunction "E4_9") (pintype "bidirectional"))
      (node (ref "R30") (pin "2") (pinfunction "2_2") (pintype "passive"))
      (node (ref "U4") (pin "9") (pinfunction "INPUT4_9") (pintype "bidirectional"))
    )
    (net (code "48") (name "P3") (class "Default")
      (node (ref "R5") (pin "1") (pinfunction "1_1") (pintype "passive"))
      (node (ref "SJ2") (pin "2") (pinfunction "2_2") (pintype "passive"))
      (node (ref "U2") (pin "17") (pinfunction "VCC3V_17") (pintype "bidirectional"))
      (node (ref "U2") (pin "47") (pinfunction "VCC3V_47") (pintype "bidirectional"))
    )
    (net (code "49") (name "P3_SW") (class "Default")
      (node (ref "J2") (pin "4") (pinfunction "4_4") (pintype "bidirectional"))
      (node (ref "J3") (pin "2") (pinfunction "2_2") (pintype "bidirectional"))
      (node (ref "SJ2") (pin "1") (pinfunction "1_1") (pintype "passive"))
    )
    (net (code "50") (name "P18_SW1") (class "Default")
      (node (ref "OK2") (pin "1") (pinfunction "A1_1") (pintype "bidirectional"))
      (node (ref "R7") (pin "1") (pinfunction "1_1") (pintype "passive"))
    )
    (net (code "51") (name "P18_SW2") (class "Default")
      (node (ref "OK2") (pin "5") (pinfunction "A3_5") (pintype "bidirectional"))
      (node (ref "R8") (pin "1") (pinfunction "1_1") (pintype "passive"))
    )
    (net (code "52") (name "P18_SW3") (class "Default")
      (node (ref "OK3") (pin "1") (pinfunction "A1_1") (pintype "bidirectional"))
      (node (ref "R9") (pin "1") (pinfunction "1_1") (pintype "passive"))
    )
    (net (code "53") (name "P18_SW4") (class "Default")
      (node (ref "OK3") (pin "5") (pinfunction "A3_5") (pintype "bidirectional"))
      (node (ref "R10") (pin "1") (pinfunction "1_1") (pintype "passive"))
    )
    (net (code "54") (name "P18_SW5") (class "Default")
      (node (ref "OK2") (pin "3") (pinfunction "A2_3") (pintype "bidirectional"))
      (node (ref "R11") (pin "1") (pinfunction "1_1") (pintype "passive"))
    )
    (net (code "55") (name "P18_SW6") (class "Default")
      (node (ref "OK2") (pin "7") (pinfunction "A4_7") (pintype "bidirectional"))
      (node (ref "R12") (pin "1") (pinfunction "1_1") (pintype "passive"))
    )
    (net (code "56") (name "P18_SW7") (class "Default")
      (node (ref "OK3") (pin "3") (pinfunction "A2_3") (pintype "bidirectional"))
      (node (ref "R13") (pin "1") (pinfunction "1_1") (pintype "passive"))
    )
    (net (code "57") (name "P18_SW8") (class "Default")
      (node (ref "OK3") (pin "7") (pinfunction "A4_7") (pintype "bidirectional"))
      (node (ref "R14") (pin "1") (pinfunction "1_1") (pintype "passive"))
    )
    (net (code "58") (name "PBATT_SW") (class "Default")
      (node (ref "J2") (pin "5") (pinfunction "5_5") (pintype "bidirectional"))
      (node (ref "J3") (pin "3") (pinfunction "3_3") (pintype "bidirectional"))
      (node (ref "SJ1") (pin "1") (pinfunction "1_1") (pintype "passive"))
    )
    (net (code "59") (name "PGND") (class "Default")
      (node (ref "C3") (pin "2") (pinfunction "2_2") (pintype "passive"))
      (node (ref "C4") (pin "2") (pinfunction "2_2") (pintype "passive"))
      (node (ref "C5") (pin "K1") (pinfunction "K_K1") (pintype "passive"))
      (node (ref "H1") (pin "P$1") (pinfunction "MOUNT_P$1") (pintype "passive"))
      (node (ref "H2") (pin "P$1") (pinfunction "MOUNT_P$1") (pintype "passive"))
      (node (ref "H3") (pin "P$1") (pinfunction "MOUNT_P$1") (pintype "passive"))
      (node (ref "HBL") (pin "P$1") (pinfunction "MOUNT_P$1") (pintype "passive"))
      (node (ref "J4") (pin "1") (pinfunction "1_1") (pintype "bidirectional"))
      (node (ref "J4") (pin "4") (pinfunction "4_4") (pintype "bidirectional"))
      (node (ref "J5") (pin "1") (pinfunction "1_1") (pintype "bidirectional"))
      (node (ref "J5") (pin "4") (pinfunction "4_4") (pintype "bidirectional"))
      (node (ref "R23") (pin "1") (pinfunction "1_1") (pintype "passive"))
      (node (ref "R24") (pin "1") (pinfunction "1_1") (pintype "passive"))
      (node (ref "R25") (pin "1") (pinfunction "1_1") (pintype "passive"))
      (node (ref "R26") (pin "1") (pinfunction "1_1") (pintype "passive"))
      (node (ref "R27") (pin "1") (pinfunction "1_1") (pintype "passive"))
      (node (ref "R28") (pin "1") (pinfunction "1_1") (pintype "passive"))
      (node (ref "R29") (pin "1") (pinfunction "1_1") (pintype "passive"))
      (node (ref "R3") (pin "2") (pinfunction "2_2") (pintype "passive"))
      (node (ref "R30") (pin "1") (pinfunction "1_1") (pintype "passive"))
      (node (ref "SJ4") (pin "2") (pinfunction "2_2") (pintype "passive"))
      (node (ref "U1") (pin "A1") (pinfunction "PGND_A1") (pintype "bidirectional"))
      (node (ref "U1") (pin "A11") (pinfunction "PGND_A11") (pintype "bidirectional"))
      (node (ref "U1") (pin "A12") (pinfunction "PGND_A12") (pintype "bidirectional"))
      (node (ref "U1") (pin "A2") (pinfunction "PGND_A2") (pintype "bidirectional"))
      (node (ref "U1") (pin "A3") (pinfunction "PGND_A3") (pintype "bidirectional"))
      (node (ref "U1") (pin "A5") (pinfunction "SENSE-_A5") (pintype "bidirectional"))
      (node (ref "U1") (pin "A7") (pinfunction "SGND_A7") (pintype "bidirectional"))
      (node (ref "U1") (pin "B1") (pinfunction "PGND_B1") (pintype "bidirectional"))
      (node (ref "U1") (pin "B10") (pinfunction "PGND_B10") (pintype "bidirectional"))
      (node (ref "U1") (pin "B11") (pinfunction "PGND_B11") (pintype "bidirectional"))
      (node (ref "U1") (pin "B12") (pinfunction "PGND_B12") (pintype "bidirectional"))
      (node (ref "U1") (pin "B2") (pinfunction "PGND_B2") (pintype "bidirectional"))
      (node (ref "U1") (pin "B3") (pinfunction "PGND_B3") (pintype "bidirectional"))
      (node (ref "U1") (pin "B4") (pinfunction "PGND_B4") (pintype "bidirectional"))
      (node (ref "U1") (pin "C1") (pinfunction "PGND_C1") (pintype "bidirectional"))
      (node (ref "U1") (pin "C10") (pinfunction "PGND_C10") (pintype "bidirectional"))
      (node (ref "U1") (pin "C11") (pinfunction "PGND_C11") (pintype "bidirectional"))
      (node (ref "U1") (pin "C12") (pinfunction "PGND_C12") (pintype "bidirectional"))
      (node (ref "U1") (pin "C2") (pinfunction "PGND_C2") (pintype "bidirectional"))
      (node (ref "U1") (pin "C3") (pinfunction "PGND_C3") (pintype "bidirectional"))
      (node (ref "U1") (pin "C4") (pinfunction "PGND_C4") (pintype "bidirectional"))
      (node (ref "U1") (pin "C5") (pinfunction "PGND_C5") (pintype "bidirectional"))
      (node (ref "U1") (pin "C6") (pinfunction "PGND_C6") (pintype "bidirectional"))
      (node (ref "U1") (pin "C7") (pinfunction "PGND_C7") (pintype "bidirectional"))
      (node (ref "U1") (pin "C8") (pinfunction "PGND_C8") (pintype "bidirectional"))
      (node (ref "U1") (pin "C9") (pinfunction "PGND_C9") (pintype "bidirectional"))
      (node (ref "U1") (pin "D1") (pinfunction "PGND_D1") (pintype "bidirectional"))
      (node (ref "U1") (pin "D10") (pinfunction "PGND_D10") (pintype "bidirectional"))
      (node (ref "U1") (pin "D11") (pinfunction "PGND_D11") (pintype "bidirectional"))
      (node (ref "U1") (pin "D12") (pinfunction "PGND_D12") (pintype "bidirectional"))
      (node (ref "U1") (pin "D2") (pinfunction "PGND_D2") (pintype "bidirectional"))
      (node (ref "U1") (pin "D3") (pinfunction "PGND_D3") (pintype "bidirectional"))
      (node (ref "U1") (pin "D4") (pinfunction "PGND_D4") (pintype "bidirectional"))
      (node (ref "U1") (pin "D5") (pinfunction "PGND_D5") (pintype "bidirectional"))
      (node (ref "U1") (pin "D6") (pinfunction "PGND_D6") (pintype "bidirectional"))
      (node (ref "U1") (pin "D7") (pinfunction "PGND_D7") (pintype "bidirectional"))
      (node (ref "U1") (pin "D8") (pinfunction "PGND_D8") (pintype "bidirectional"))
      (node (ref "U1") (pin "D9") (pinfunction "PGND_D9") (pintype "bidirectional"))
      (node (ref "U1") (pin "E10") (pinfunction "PGND_E10") (pintype "bidirectional"))
      (node (ref "U1") (pin "E11") (pinfunction "PGND_E11") (pintype "bidirectional"))
      (node (ref "U1") (pin "E12") (pinfunction "PGND_E12") (pintype "bidirectional"))
      (node (ref "U1") (pin "E3") (pinfunction "PGND_E3") (pintype "bidirectional"))
      (node (ref "U1") (pin "E4") (pinfunction "PGND_E4") (pintype "bidirectional"))
      (node (ref "U1") (pin "E5") (pinfunction "PGND_E5") (pintype "bidirectional"))
      (node (ref "U1") (pin "E6") (pinfunction "PGND_E6") (pintype "bidirectional"))
      (node (ref "U1") (pin "E7") (pinfunction "PGND_E7") (pintype "bidirectional"))
      (node (ref "U1") (pin "E8") (pinfunction "PGND_E8") (pintype "bidirectional"))
      (node (ref "U1") (pin "E9") (pinfunction "PGND_E9") (pintype "bidirectional"))
      (node (ref "U3") (pin "1") (pinfunction "GND_1") (pintype "bidirectional"))
      (node (ref "U3") (pin "10") (pinfunction "GND_10") (pintype "bidirectional"))
      (node (ref "U4") (pin "1") (pinfunction "GND_1") (pintype "bidirectional"))
      (node (ref "U4") (pin "10") (pinfunction "GND_10") (pintype "bidirectional"))
    )
    (net (code "60") (name "PGOOD_PMA(OUT)") (class "Default")
      (node (ref "J2") (pin "3") (pinfunction "3_3") (pintype "bidirectional"))
      (node (ref "U1") (pin "B5") (pinfunction "PGOOD_B5") (pintype "bidirectional"))
    )
    (net (code "61") (name "RSENSE") (class "Default")
      (node (ref "R3") (pin "1") (pinfunction "1_1") (pintype "passive"))
      (node (ref "U1") (pin "A4") (pinfunction "SENSE+_A4") (pintype "bidirectional"))
      (node (ref "U1") (pin "F10") (pinfunction "R_SENSE_F10") (pintype "bidirectional"))
      (node (ref "U1") (pin "F11") (pinfunction "R_SENSE_F11") (pintype "bidirectional"))
      (node (ref "U1") (pin "F12") (pinfunction "R_SENSE_F12") (pintype "bidirectional"))
      (node (ref "U1") (pin "G10") (pinfunction "R_SENSE_G10") (pintype "bidirectional"))
      (node (ref "U1") (pin "G11") (pinfunction "R_SENSE_G11") (pintype "bidirectional"))
      (node (ref "U1") (pin "G12") (pinfunction "R_SENSE_G12") (pintype "bidirectional"))
      (node (ref "U1") (pin "G5") (pinfunction "R_SENSE_G5") (pintype "bidirectional"))
      (node (ref "U1") (pin "G6") (pinfunction "R_SENSE_G6") (pintype "bidirectional"))
      (node (ref "U1") (pin "G7") (pinfunction "R_SENSE_G7") (pintype "bidirectional"))
      (node (ref "U1") (pin "G8") (pinfunction "R_SENSE_G8") (pintype "bidirectional"))
      (node (ref "U1") (pin "G9") (pinfunction "R_SENSE_G9") (pintype "bidirectional"))
      (node (ref "U1") (pin "H10") (pinfunction "R_SENSE_H10") (pintype "bidirectional"))
      (node (ref "U1") (pin "H11") (pinfunction "R_SENSE_H11") (pintype "bidirectional"))
      (node (ref "U1") (pin "H12") (pinfunction "R_SENSE_H12") (pintype "bidirectional"))
      (node (ref "U1") (pin "H5") (pinfunction "R_SENSE_H5") (pintype "bidirectional"))
      (node (ref "U1") (pin "H6") (pinfunction "R_SENSE_H6") (pintype "bidirectional"))
      (node (ref "U1") (pin "H7") (pinfunction "R_SENSE_H7") (pintype "bidirectional"))
      (node (ref "U1") (pin "H8") (pinfunction "R_SENSE_H8") (pintype "bidirectional"))
      (node (ref "U1") (pin "H9") (pinfunction "R_SENSE_H9") (pintype "bidirectional"))
      (node (ref "U1") (pin "J5") (pinfunction "R_SENSE_J5") (pintype "bidirectional"))
      (node (ref "U1") (pin "J6") (pinfunction "R_SENSE_J6") (pintype "bidirectional"))
      (node (ref "U1") (pin "J7") (pinfunction "R_SENSE_J7") (pintype "bidirectional"))
      (node (ref "U1") (pin "K5") (pinfunction "R_SENSE_K5") (pintype "bidirectional"))
      (node (ref "U1") (pin "K6") (pinfunction "R_SENSE_K6") (pintype "bidirectional"))
      (node (ref "U1") (pin "L5") (pinfunction "R_SENSE_L5") (pintype "bidirectional"))
      (node (ref "U1") (pin "L6") (pinfunction "R_SENSE_L6") (pintype "bidirectional"))
      (node (ref "U1") (pin "M5") (pinfunction "R_SENSE_M5") (pintype "bidirectional"))
      (node (ref "U1") (pin "M6") (pinfunction "R_SENSE_M6") (pintype "bidirectional"))
    )
    (net (code "62") (name "SGND") (class "Default")
      (node (ref "J3") (pin "6") (pinfunction "6_6") (pintype "bidirectional"))
      (node (ref "J4") (pin "12") (pinfunction "12_12") (pintype "bidirectional"))
      (node (ref "J4") (pin "9") (pinfunction "9_9") (pintype "bidirectional"))
      (node (ref "J5") (pin "12") (pinfunction "12_12") (pintype "bidirectional"))
      (node (ref "J5") (pin "9") (pinfunction "9_9") (pintype "bidirectional"))
      (node (ref "OK1") (pin "15") (pinfunction "E1_15") (pintype "bidirectional"))
      (node (ref "OK2") (pin "2") (pinfunction "K1_2") (pintype "bidirectional"))
      (node (ref "OK2") (pin "4") (pinfunction "K2_4") (pintype "bidirectional"))
      (node (ref "OK2") (pin "6") (pinfunction "K3_6") (pintype "bidirectional"))
      (node (ref "OK2") (pin "8") (pinfunction "K4_8") (pintype "bidirectional"))
      (node (ref "OK3") (pin "2") (pinfunction "K1_2") (pintype "bidirectional"))
      (node (ref "OK3") (pin "4") (pinfunction "K2_4") (pintype "bidirectional"))
      (node (ref "OK3") (pin "6") (pinfunction "K3_6") (pintype "bidirectional"))
      (node (ref "OK3") (pin "8") (pinfunction "K4_8") (pintype "bidirectional"))
      (node (ref "R2") (pin "2") (pinfunction "2_2") (pintype "passive"))
      (node (ref "SJ3") (pin "2") (pinfunction "2_2") (pintype "passive"))
    )
    (net (code "63") (name "SW_P18H1") (class "Default")
      (node (ref "R11") (pin "2") (pinfunction "2_2") (pintype "passive"))
      (node (ref "U2") (pin "35") (pinfunction "SDHC_DAT0_35") (pintype "bidirectional"))
    )
    (net (code "64") (name "SW_P18H2") (class "Default")
      (node (ref "R12") (pin "2") (pinfunction "2_2") (pintype "passive"))
      (node (ref "U2") (pin "34") (pinfunction "UART1_TX_34") (pintype "bidirectional"))
    )
    (net (code "65") (name "SW_P18H3") (class "Default")
      (node (ref "R13") (pin "2") (pinfunction "2_2") (pintype "passive"))
      (node (ref "U2") (pin "33") (pinfunction "SDHC_CMD_33") (pintype "bidirectional"))
    )
    (net (code "66") (name "SW_P18H4") (class "Default")
      (node (ref "R14") (pin "2") (pinfunction "2_2") (pintype "passive"))
      (node (ref "U2") (pin "32") (pinfunction "UART1_RX_32") (pintype "bidirectional"))
    )
    (net (code "67") (name "SW_P18L1") (class "Default")
      (node (ref "R7") (pin "2") (pinfunction "2_2") (pintype "passive"))
      (node (ref "U2") (pin "39") (pinfunction "SDHC_DAT2_39") (pintype "bidirectional"))
    )
    (net (code "68") (name "SW_P18L2") (class "Default")
      (node (ref "R8") (pin "2") (pinfunction "2_2") (pintype "passive"))
      (node (ref "U2") (pin "38") (pinfunction "UART1_CTS_38") (pintype "bidirectional"))
    )
    (net (code "69") (name "SW_P18L3") (class "Default")
      (node (ref "R9") (pin "2") (pinfunction "2_2") (pintype "passive"))
      (node (ref "U2") (pin "37") (pinfunction "SDHC_DAT1_37") (pintype "bidirectional"))
    )
    (net (code "70") (name "SW_P18L4") (class "Default")
      (node (ref "R10") (pin "2") (pinfunction "2_2") (pintype "passive"))
      (node (ref "U2") (pin "36") (pinfunction "UART1_RTS_36") (pintype "bidirectional"))
    )
    (net (code "71") (name "SW_RUNPMA") (class "Default")
      (node (ref "U1") (pin "A8") (pinfunction "RUN_A8") (pintype "bidirectional"))
      (node (ref "U2") (pin "23") (pinfunction "T2IN_23") (pintype "bidirectional"))
    )
    (net (code "72") (name "SW_TP1") (class "Default")
      (node (ref "J3") (pin "7") (pinfunction "7_7") (pintype "bidirectional"))
      (node (ref "OK1") (pin "2") (pinfunction "K1_2") (pintype "bidirectional"))
      (node (ref "U2") (pin "31") (pinfunction "SDHC_CLK_31") (pintype "bidirectional"))
    )
    (net (code "73") (name "TP1_OUT") (class "Default")
      (node (ref "J3") (pin "8") (pinfunction "8_8") (pintype "bidirectional"))
      (node (ref "J4") (pin "3") (pinfunction "3_3") (pintype "bidirectional"))
      (node (ref "J4") (pin "6") (pinfunction "6_6") (pintype "bidirectional"))
      (node (ref "J5") (pin "3") (pinfunction "3_3") (pintype "bidirectional"))
      (node (ref "J5") (pin "6") (pinfunction "6_6") (pintype "bidirectional"))
      (node (ref "OK1") (pin "16") (pinfunction "C1_16") (pintype "bidirectional"))
      (node (ref "R6") (pin "1") (pinfunction "1_1") (pintype "passive"))
    )
    (net (code "74") (name "VBATT_IN") (class "Default")
      (node (ref "C1") (pin "A1") (pinfunction "A_A1") (pintype "passive"))
      (node (ref "L1") (pin "1") (pinfunction "1_1") (pintype "bidirectional"))
      (node (ref "SJ1") (pin "2") (pinfunction "2_2") (pintype "passive"))
    )
    (net (code "75") (name "VIN") (class "Default")
      (node (ref "C2") (pin "1") (pinfunction "1_1") (pintype "passive"))
      (node (ref "L1") (pin "2") (pinfunction "2_2") (pintype "bidirectional"))
      (node (ref "U1") (pin "J10") (pinfunction "V_IN_J10") (pintype "bidirectional"))
      (node (ref "U1") (pin "J11") (pinfunction "V_IN_J11") (pintype "bidirectional"))
      (node (ref "U1") (pin "J12") (pinfunction "V_IN_J12") (pintype "bidirectional"))
      (node (ref "U1") (pin "K10") (pinfunction "V_IN_K10") (pintype "bidirectional"))
      (node (ref "U1") (pin "K11") (pinfunction "V_IN_K11") (pintype "bidirectional"))
      (node (ref "U1") (pin "K12") (pinfunction "V_IN_K12") (pintype "bidirectional"))
      (node (ref "U1") (pin "L10") (pinfunction "V_IN_L10") (pintype "bidirectional"))
      (node (ref "U1") (pin "L11") (pinfunction "V_IN_L11") (pintype "bidirectional"))
      (node (ref "U1") (pin "L12") (pinfunction "V_IN_L12") (pintype "bidirectional"))
      (node (ref "U1") (pin "M10") (pinfunction "V_IN_M10") (pintype "bidirectional"))
      (node (ref "U1") (pin "M11") (pinfunction "V_IN_M11") (pintype "bidirectional"))
      (node (ref "U1") (pin "M12") (pinfunction "V_IN_M12") (pintype "bidirectional"))
    )
    (net (code "76") (name "VOUT") (class "Default")
      (node (ref "C3") (pin "1") (pinfunction "1_1") (pintype "passive"))
      (node (ref "C4") (pin "1") (pinfunction "1_1") (pintype "passive"))
      (node (ref "L3") (pin "1") (pinfunction "1_1") (pintype "bidirectional"))
      (node (ref "U1") (pin "E1") (pinfunction "V_OUT_E1") (pintype "bidirectional"))
      (node (ref "U1") (pin "E2") (pinfunction "V_OUT_E2") (pintype "bidirectional"))
      (node (ref "U1") (pin "F1") (pinfunction "V_OUT_F1") (pintype "bidirectional"))
      (node (ref "U1") (pin "F2") (pinfunction "V_OUT_F2") (pintype "bidirectional"))
      (node (ref "U1") (pin "F3") (pinfunction "V_OUT_F3") (pintype "bidirectional"))
      (node (ref "U1") (pin "F4") (pinfunction "V_OUT_F4") (pintype "bidirectional"))
      (node (ref "U1") (pin "G1") (pinfunction "V_OUT_G1") (pintype "bidirectional"))
      (node (ref "U1") (pin "G2") (pinfunction "V_OUT_G2") (pintype "bidirectional"))
      (node (ref "U1") (pin "G3") (pinfunction "V_OUT_G3") (pintype "bidirectional"))
      (node (ref "U1") (pin "G4") (pinfunction "V_OUT_G4") (pintype "bidirectional"))
      (node (ref "U1") (pin "H2") (pinfunction "V_OUT_H2") (pintype "bidirectional"))
      (node (ref "U1") (pin "H3") (pinfunction "V_OUT_H3") (pintype "bidirectional"))
      (node (ref "U1") (pin "H4") (pinfunction "V_OUT_H4") (pintype "bidirectional"))
      (node (ref "U1") (pin "VOUT") (pinfunction "V_OUT_VOUT") (pintype "bidirectional"))
    )
    (net (code "77") (name "VOUTA") (class "Default")
      (node (ref "C5") (pin "A1") (pinfunction "A_A1") (pintype "passive"))
      (node (ref "L3") (pin "2") (pinfunction "2_2") (pintype "bidirectional"))
      (node (ref "Q1") (pin "D") (pinfunction "D_D") (pintype "bidirectional"))
      (node (ref "Q3") (pin "D") (pinfunction "D_D") (pintype "bidirectional"))
      (node (ref "Q5") (pin "D") (pinfunction "D_D") (pintype "bidirectional"))
      (node (ref "Q7") (pin "D") (pinfunction "D_D") (pintype "bidirectional"))
      (node (ref "R15") (pin "1") (pinfunction "1_1") (pintype "passive"))
      (node (ref "R16") (pin "1") (pinfunction "1_1") (pintype "passive"))
      (node (ref "R17") (pin "1") (pinfunction "1_1") (pintype "passive"))
      (node (ref "R18") (pin "1") (pinfunction "1_1") (pintype "passive"))
      (node (ref "R19") (pin "1") (pinfunction "1_1") (pintype "passive"))
      (node (ref "R20") (pin "1") (pinfunction "1_1") (pintype "passive"))
      (node (ref "R21") (pin "1") (pinfunction "1_1") (pintype "passive"))
      (node (ref "R22") (pin "1") (pinfunction "1_1") (pintype "passive"))
      (node (ref "R31") (pin "2") (pinfunction "2_2") (pintype "passive"))
      (node (ref "R32") (pin "2") (pinfunction "2_2") (pintype "passive"))
      (node (ref "R33") (pin "2") (pinfunction "2_2") (pintype "passive"))
      (node (ref "R34") (pin "2") (pinfunction "2_2") (pintype "passive"))
      (node (ref "U3") (pin "11") (pinfunction "V+_11") (pintype "bidirectional"))
      (node (ref "U3") (pin "13") (pinfunction "SENSE4_13") (pintype "bidirectional"))
      (node (ref "U3") (pin "15") (pinfunction "SENSE3_15") (pintype "bidirectional"))
      (node (ref "U3") (pin "17") (pinfunction "SENSE2_17") (pintype "bidirectional"))
      (node (ref "U3") (pin "19") (pinfunction "SENSE1_19") (pintype "bidirectional"))
      (node (ref "U3") (pin "20") (pinfunction "V+_20") (pintype "bidirectional"))
      (node (ref "U4") (pin "11") (pinfunction "V+_11") (pintype "bidirectional"))
      (node (ref "U4") (pin "13") (pinfunction "SENSE4_13") (pintype "bidirectional"))
      (node (ref "U4") (pin "15") (pinfunction "SENSE3_15") (pintype "bidirectional"))
      (node (ref "U4") (pin "17") (pinfunction "SENSE2_17") (pintype "bidirectional"))
      (node (ref "U4") (pin "19") (pinfunction "SENSE1_19") (pintype "bidirectional"))
      (node (ref "U4") (pin "20") (pinfunction "V+_20") (pintype "bidirectional"))
    )
    (net (code "78") (name "unconnected-(J1-+5V_SW-Pad33)") (class "Default")
      (node (ref "J1") (pin "33") (pinfunction "+5V_SW_33") (pintype "bidirectional"))
    )
    (net (code "79") (name "unconnected-(J1-+5V_SYS-Pad77)") (class "Default")
      (node (ref "J1") (pin "77") (pinfunction "+5V_SYS_77") (pintype "bidirectional"))
    )
    (net (code "80") (name "unconnected-(J1-+5V_SYS-Pad78)") (class "Default")
      (node (ref "J1") (pin "78") (pinfunction "+5V_SYS_78") (pintype "bidirectional"))
    )
    (net (code "81") (name "unconnected-(J1-+5V_USB-Pad32)") (class "Default")
      (node (ref "J1") (pin "32") (pinfunction "+5V_USB_32") (pintype "bidirectional"))
    )
    (net (code "82") (name "unconnected-(J1--CTS_MHX-Pad35)") (class "Default")
      (node (ref "J1") (pin "35") (pinfunction "-CTS_MHX_35") (pintype "bidirectional"))
    )
    (net (code "83") (name "unconnected-(J1--DSR_MHX-Pad37)") (class "Default")
      (node (ref "J1") (pin "37") (pinfunction "-DSR_MHX_37") (pintype "bidirectional"))
    )
    (net (code "84") (name "unconnected-(J1--DTR_MHX-Pad38)") (class "Default")
      (node (ref "J1") (pin "38") (pinfunction "-DTR_MHX_38") (pintype "bidirectional"))
    )
    (net (code "85") (name "unconnected-(J1--FAULT-Pad25)") (class "Default")
      (node (ref "J1") (pin "25") (pinfunction "-FAULT_25") (pintype "bidirectional"))
    )
    (net (code "86") (name "unconnected-(J1--RESET-Pad29)") (class "Default")
      (node (ref "J1") (pin "29") (pinfunction "-RESET_29") (pintype "bidirectional"))
    )
    (net (code "87") (name "unconnected-(J1--RST_MHX-Pad34)") (class "Default")
      (node (ref "J1") (pin "34") (pinfunction "-RST_MHX_34") (pintype "bidirectional"))
    )
    (net (code "88") (name "unconnected-(J1--RTS_MHX-Pad36)") (class "Default")
      (node (ref "J1") (pin "36") (pinfunction "-RTS_MHX_36") (pintype "bidirectional"))
    )
    (net (code "89") (name "unconnected-(J1-OFF_VCC-Pad31)") (class "Default")
      (node (ref "J1") (pin "31") (pinfunction "OFF_VCC_31") (pintype "bidirectional"))
    )
    (net (code "90") (name "unconnected-(J1-P1.0-Pad68)") (class "Default")
      (node (ref "J1") (pin "68") (pinfunction "P1.0_68") (pintype "bidirectional"))
    )
    (net (code "91") (name "unconnected-(J1-P1.1-Pad67)") (class "Default")
      (node (ref "J1") (pin "67") (pinfunction "P1.1_67") (pintype "bidirectional"))
    )
    (net (code "92") (name "unconnected-(J1-P1.2-Pad66)") (class "Default")
      (node (ref "J1") (pin "66") (pinfunction "P1.2_66") (pintype "bidirectional"))
    )
    (net (code "93") (name "unconnected-(J1-P1.3-Pad65)") (class "Default")
      (node (ref "J1") (pin "65") (pinfunction "P1.3_65") (pintype "bidirectional"))
    )
    (net (code "94") (name "unconnected-(J1-P1.4-Pad64)") (class "Default")
      (node (ref "J1") (pin "64") (pinfunction "P1.4_64") (pintype "bidirectional"))
    )
    (net (code "95") (name "unconnected-(J1-P1.5-Pad63)") (class "Default")
      (node (ref "J1") (pin "63") (pinfunction "P1.5_63") (pintype "bidirectional"))
    )
    (net (code "96") (name "unconnected-(J1-P1.6-Pad62)") (class "Default")
      (node (ref "J1") (pin "62") (pinfunction "P1.6_62") (pintype "bidirectional"))
    )
    (net (code "97") (name "unconnected-(J1-P1.7-Pad61)") (class "Default")
      (node (ref "J1") (pin "61") (pinfunction "P1.7_61") (pintype "bidirectional"))
    )
    (net (code "98") (name "unconnected-(J1-P2.0-Pad76)") (class "Default")
      (node (ref "J1") (pin "76") (pinfunction "P2.0_76") (pintype "bidirectional"))
    )
    (net (code "99") (name "unconnected-(J1-P2.1-Pad75)") (class "Default")
      (node (ref "J1") (pin "75") (pinfunction "P2.1_75") (pintype "bidirectional"))
    )
    (net (code "100") (name "unconnected-(J1-P2.2-Pad74)") (class "Default")
      (node (ref "J1") (pin "74") (pinfunction "P2.2_74") (pintype "bidirectional"))
    )
    (net (code "101") (name "unconnected-(J1-P2.3-Pad73)") (class "Default")
      (node (ref "J1") (pin "73") (pinfunction "P2.3_73") (pintype "bidirectional"))
    )
    (net (code "102") (name "unconnected-(J1-P2.4-Pad72)") (class "Default")
      (node (ref "J1") (pin "72") (pinfunction "P2.4_72") (pintype "bidirectional"))
    )
    (net (code "103") (name "unconnected-(J1-P2.5-Pad71)") (class "Default")
      (node (ref "J1") (pin "71") (pinfunction "P2.5_71") (pintype "bidirectional"))
    )
    (net (code "104") (name "unconnected-(J1-P2.6-Pad70)") (class "Default")
      (node (ref "J1") (pin "70") (pinfunction "P2.6_70") (pintype "bidirectional"))
    )
    (net (code "105") (name "unconnected-(J1-P2.7-Pad69)") (class "Default")
      (node (ref "J1") (pin "69") (pinfunction "P2.7_69") (pintype "bidirectional"))
    )
    (net (code "106") (name "unconnected-(J1-P3.0-Pad24)") (class "Default")
      (node (ref "J1") (pin "24") (pinfunction "P3.0_24") (pintype "bidirectional"))
    )
    (net (code "107") (name "unconnected-(J1-P3.1-Pad23)") (class "Default")
      (node (ref "J1") (pin "23") (pinfunction "P3.1_23") (pintype "bidirectional"))
    )
    (net (code "108") (name "unconnected-(J1-P3.2-Pad22)") (class "Default")
      (node (ref "J1") (pin "22") (pinfunction "P3.2_22") (pintype "bidirectional"))
    )
    (net (code "109") (name "unconnected-(J1-P3.3-Pad21)") (class "Default")
      (node (ref "J1") (pin "21") (pinfunction "P3.3_21") (pintype "bidirectional"))
    )
    (net (code "110") (name "unconnected-(J1-P3.4-Pad20)") (class "Default")
      (node (ref "J1") (pin "20") (pinfunction "P3.4_20") (pintype "bidirectional"))
    )
    (net (code "111") (name "unconnected-(J1-P3.5-Pad19)") (class "Default")
      (node (ref "J1") (pin "19") (pinfunction "P3.5_19") (pintype "bidirectional"))
    )
    (net (code "112") (name "unconnected-(J1-P3.6-Pad18)") (class "Default")
      (node (ref "J1") (pin "18") (pinfunction "P3.6_18") (pintype "bidirectional"))
    )
    (net (code "113") (name "unconnected-(J1-P3.7-Pad17)") (class "Default")
      (node (ref "J1") (pin "17") (pinfunction "P3.7_17") (pintype "bidirectional"))
    )
    (net (code "114") (name "unconnected-(J1-P4.0-Pad16)") (class "Default")
      (node (ref "J1") (pin "16") (pinfunction "P4.0_16") (pintype "bidirectional"))
    )
    (net (code "115") (name "unconnected-(J1-P4.1-Pad15)") (class "Default")
      (node (ref "J1") (pin "15") (pinfunction "P4.1_15") (pintype "bidirectional"))
    )
    (net (code "116") (name "unconnected-(J1-P4.2-Pad14)") (class "Default")
      (node (ref "J1") (pin "14") (pinfunction "P4.2_14") (pintype "bidirectional"))
    )
    (net (code "117") (name "unconnected-(J1-P4.3-Pad13)") (class "Default")
      (node (ref "J1") (pin "13") (pinfunction "P4.3_13") (pintype "bidirectional"))
    )
    (net (code "118") (name "unconnected-(J1-P4.4-Pad12)") (class "Default")
      (node (ref "J1") (pin "12") (pinfunction "P4.4_12") (pintype "bidirectional"))
    )
    (net (code "119") (name "unconnected-(J1-P4.5-Pad11)") (class "Default")
      (node (ref "J1") (pin "11") (pinfunction "P4.5_11") (pintype "bidirectional"))
    )
    (net (code "120") (name "unconnected-(J1-P4.6-Pad10)") (class "Default")
      (node (ref "J1") (pin "10") (pinfunction "P4.6_10") (pintype "bidirectional"))
    )
    (net (code "121") (name "unconnected-(J1-P4.7-Pad9)") (class "Default")
      (node (ref "J1") (pin "9") (pinfunction "P4.7_9") (pintype "bidirectional"))
    )
    (net (code "122") (name "unconnected-(J1-P5.0-Pad8)") (class "Default")
      (node (ref "J1") (pin "8") (pinfunction "P5.0_8") (pintype "bidirectional"))
    )
    (net (code "123") (name "unconnected-(J1-P5.1-Pad7)") (class "Default")
      (node (ref "J1") (pin "7") (pinfunction "P5.1_7") (pintype "bidirectional"))
    )
    (net (code "124") (name "unconnected-(J1-P5.2-Pad6)") (class "Default")
      (node (ref "J1") (pin "6") (pinfunction "P5.2_6") (pintype "bidirectional"))
    )
    (net (code "125") (name "unconnected-(J1-P5.3-Pad5)") (class "Default")
      (node (ref "J1") (pin "5") (pinfunction "P5.3_5") (pintype "bidirectional"))
    )
    (net (code "126") (name "unconnected-(J1-P5.4-Pad4)") (class "Default")
      (node (ref "J1") (pin "4") (pinfunction "P5.4_4") (pintype "bidirectional"))
    )
    (net (code "127") (name "unconnected-(J1-P5.5-Pad3)") (class "Default")
      (node (ref "J1") (pin "3") (pinfunction "P5.5_3") (pintype "bidirectional"))
    )
    (net (code "128") (name "unconnected-(J1-P5.6-Pad2)") (class "Default")
      (node (ref "J1") (pin "2") (pinfunction "P5.6_2") (pintype "bidirectional"))
    )
    (net (code "129") (name "unconnected-(J1-P5.7-Pad1)") (class "Default")
      (node (ref "J1") (pin "1") (pinfunction "P5.7_1") (pintype "bidirectional"))
    )
    (net (code "130") (name "unconnected-(J1-P6.0-Pad60)") (class "Default")
      (node (ref "J1") (pin "60") (pinfunction "P6.0_60") (pintype "bidirectional"))
    )
    (net (code "131") (name "unconnected-(J1-P6.1-Pad59)") (class "Default")
      (node (ref "J1") (pin "59") (pinfunction "P6.1_59") (pintype "bidirectional"))
    )
    (net (code "132") (name "unconnected-(J1-P6.2-Pad58)") (class "Default")
      (node (ref "J1") (pin "58") (pinfunction "P6.2_58") (pintype "bidirectional"))
    )
    (net (code "133") (name "unconnected-(J1-P6.3-Pad57)") (class "Default")
      (node (ref "J1") (pin "57") (pinfunction "P6.3_57") (pintype "bidirectional"))
    )
    (net (code "134") (name "unconnected-(J1-P6.4-Pad56)") (class "Default")
      (node (ref "J1") (pin "56") (pinfunction "P6.4_56") (pintype "bidirectional"))
    )
    (net (code "135") (name "unconnected-(J1-P6.5-Pad55)") (class "Default")
      (node (ref "J1") (pin "55") (pinfunction "P6.5_55") (pintype "bidirectional"))
    )
    (net (code "136") (name "unconnected-(J1-P6.6-Pad54)") (class "Default")
      (node (ref "J1") (pin "54") (pinfunction "P6.6_54") (pintype "bidirectional"))
    )
    (net (code "137") (name "unconnected-(J1-P6.7-Pad53)") (class "Default")
      (node (ref "J1") (pin "53") (pinfunction "P6.7_53") (pintype "bidirectional"))
    )
    (net (code "138") (name "unconnected-(J1-RSVD0-Pad44)") (class "Default")
      (node (ref "J1") (pin "44") (pinfunction "RSVD0_44") (pintype "bidirectional"))
    )
    (net (code "139") (name "unconnected-(J1-RSVD1-Pad45)") (class "Default")
      (node (ref "J1") (pin "45") (pinfunction "RSVD1_45") (pintype "bidirectional"))
    )
    (net (code "140") (name "unconnected-(J1-RSVD2-Pad46)") (class "Default")
      (node (ref "J1") (pin "46") (pinfunction "RSVD2_46") (pintype "bidirectional"))
    )
    (net (code "141") (name "unconnected-(J1-RXD_MHX-Pad40)") (class "Default")
      (node (ref "J1") (pin "40") (pinfunction "RXD_MHX_40") (pintype "bidirectional"))
    )
    (net (code "142") (name "unconnected-(J1-SENSE-Pad27)") (class "Default")
      (node (ref "J1") (pin "27") (pinfunction "SENSE_27") (pintype "bidirectional"))
    )
    (net (code "143") (name "unconnected-(J1-SW0-Pad85)") (class "Default")
      (node (ref "J1") (pin "85") (pinfunction "SW0_85") (pintype "bidirectional"))
    )
    (net (code "144") (name "unconnected-(J1-SW0-Pad86)") (class "Default")
      (node (ref "J1") (pin "86") (pinfunction "SW0_86") (pintype "bidirectional"))
    )
    (net (code "145") (name "unconnected-(J1-SW1-Pad87)") (class "Default")
      (node (ref "J1") (pin "87") (pinfunction "SW1_87") (pintype "bidirectional"))
    )
    (net (code "146") (name "unconnected-(J1-SW1-Pad88)") (class "Default")
      (node (ref "J1") (pin "88") (pinfunction "SW1_88") (pintype "bidirectional"))
    )
    (net (code "147") (name "unconnected-(J1-SW2-Pad89)") (class "Default")
      (node (ref "J1") (pin "89") (pinfunction "SW2_89") (pintype "bidirectional"))
    )
    (net (code "148") (name "unconnected-(J1-SW2-Pad90)") (class "Default")
      (node (ref "J1") (pin "90") (pinfunction "SW2_90") (pintype "bidirectional"))
    )
    (net (code "149") (name "unconnected-(J1-SW3-Pad91)") (class "Default")
      (node (ref "J1") (pin "91") (pinfunction "SW3_91") (pintype "bidirectional"))
    )
    (net (code "150") (name "unconnected-(J1-SW3-Pad92)") (class "Default")
      (node (ref "J1") (pin "92") (pinfunction "SW3_92") (pintype "bidirectional"))
    )
    (net (code "151") (name "unconnected-(J1-SW4-Pad93)") (class "Default")
      (node (ref "J1") (pin "93") (pinfunction "SW4_93") (pintype "bidirectional"))
    )
    (net (code "152") (name "unconnected-(J1-SW4-Pad94)") (class "Default")
      (node (ref "J1") (pin "94") (pinfunction "SW4_94") (pintype "bidirectional"))
    )
    (net (code "153") (name "unconnected-(J1-SW5-Pad95)") (class "Default")
      (node (ref "J1") (pin "95") (pinfunction "SW5_95") (pintype "bidirectional"))
    )
    (net (code "154") (name "unconnected-(J1-SW5-Pad96)") (class "Default")
      (node (ref "J1") (pin "96") (pinfunction "SW5_96") (pintype "bidirectional"))
    )
    (net (code "155") (name "unconnected-(J1-TXD_MHX-Pad39)") (class "Default")
      (node (ref "J1") (pin "39") (pinfunction "TXD_MHX_39") (pintype "bidirectional"))
    )
    (net (code "156") (name "unconnected-(J1-USER0-Pad47)") (class "Default")
      (node (ref "J1") (pin "47") (pinfunction "USER0_47") (pintype "bidirectional"))
    )
    (net (code "157") (name "unconnected-(J1-USER1-Pad48)") (class "Default")
      (node (ref "J1") (pin "48") (pinfunction "USER1_48") (pintype "bidirectional"))
    )
    (net (code "158") (name "unconnected-(J1-USER2-Pad49)") (class "Default")
      (node (ref "J1") (pin "49") (pinfunction "USER2_49") (pintype "bidirectional"))
    )
    (net (code "159") (name "unconnected-(J1-USER3-Pad50)") (class "Default")
      (node (ref "J1") (pin "50") (pinfunction "USER3_50") (pintype "bidirectional"))
    )
    (net (code "160") (name "unconnected-(J1-USER4-Pad51)") (class "Default")
      (node (ref "J1") (pin "51") (pinfunction "USER4_51") (pintype "bidirectional"))
    )
    (net (code "161") (name "unconnected-(J1-USER5-Pad52)") (class "Default")
      (node (ref "J1") (pin "52") (pinfunction "USER5_52") (pintype "bidirectional"))
    )
    (net (code "162") (name "unconnected-(J1-USER6-Pad99)") (class "Default")
      (node (ref "J1") (pin "99") (pinfunction "USER6_99") (pintype "bidirectional"))
    )
    (net (code "163") (name "unconnected-(J1-USER7-Pad100)") (class "Default")
      (node (ref "J1") (pin "100") (pinfunction "USER7_100") (pintype "bidirectional"))
    )
    (net (code "164") (name "unconnected-(J1-USER8-Pad101)") (class "Default")
      (node (ref "J1") (pin "101") (pinfunction "USER8_101") (pintype "bidirectional"))
    )
    (net (code "165") (name "unconnected-(J1-USER9-Pad102)") (class "Default")
      (node (ref "J1") (pin "102") (pinfunction "USER9_102") (pintype "bidirectional"))
    )
    (net (code "166") (name "unconnected-(J1-USER10-Pad103)") (class "Default")
      (node (ref "J1") (pin "103") (pinfunction "USER10_103") (pintype "bidirectional"))
    )
    (net (code "167") (name "unconnected-(J1-USER11-Pad104)") (class "Default")
      (node (ref "J1") (pin "104") (pinfunction "USER11_104") (pintype "bidirectional"))
    )
    (net (code "168") (name "unconnected-(J1-VBACKUP-Pad42)") (class "Default")
      (node (ref "J1") (pin "42") (pinfunction "VBACKUP_42") (pintype "bidirectional"))
    )
    (net (code "169") (name "unconnected-(J1-VBATT-Pad97)") (class "Default")
      (node (ref "J1") (pin "97") (pinfunction "VBATT_97") (pintype "bidirectional"))
    )
    (net (code "170") (name "unconnected-(J1-VBATT-Pad98)") (class "Default")
      (node (ref "J1") (pin "98") (pinfunction "VBATT_98") (pintype "bidirectional"))
    )
    (net (code "171") (name "unconnected-(J1-VCC_SYS-Pad79)") (class "Default")
      (node (ref "J1") (pin "79") (pinfunction "VCC_SYS_79") (pintype "bidirectional"))
    )
    (net (code "172") (name "unconnected-(J1-VCC_SYS-Pad80)") (class "Default")
      (node (ref "J1") (pin "80") (pinfunction "VCC_SYS_80") (pintype "bidirectional"))
    )
    (net (code "173") (name "unconnected-(J1-VEREF+-Pad28)") (class "Default")
      (node (ref "J1") (pin "28") (pinfunction "VEREF+_28") (pintype "bidirectional"))
    )
    (net (code "174") (name "unconnected-(J1-VREF+-Pad26)") (class "Default")
      (node (ref "J1") (pin "26") (pinfunction "VREF+_26") (pintype "bidirectional"))
    )
    (net (code "175") (name "unconnected-(J1-VREF--Pad30)") (class "Default")
      (node (ref "J1") (pin "30") (pinfunction "VREF-_30") (pintype "bidirectional"))
    )
    (net (code "176") (name "unconnected-(J2-Pad6)") (class "Default")
      (node (ref "J2") (pin "6") (pinfunction "6_6") (pintype "bidirectional"))
    )
    (net (code "177") (name "unconnected-(J4-Pad2)") (class "Default")
      (node (ref "J4") (pin "2") (pinfunction "2_2") (pintype "bidirectional"))
    )
    (net (code "178") (name "unconnected-(J4-Pad5)") (class "Default")
      (node (ref "J4") (pin "5") (pinfunction "5_5") (pintype "bidirectional"))
    )
    (net (code "179") (name "unconnected-(J5-Pad2)") (class "Default")
      (node (ref "J5") (pin "2") (pinfunction "2_2") (pintype "bidirectional"))
    )
    (net (code "180") (name "unconnected-(J5-Pad5)") (class "Default")
      (node (ref "J5") (pin "5") (pinfunction "5_5") (pintype "bidirectional"))
    )
    (net (code "181") (name "unconnected-(OK1-A2-Pad3)") (class "Default")
      (node (ref "OK1") (pin "3") (pinfunction "A2_3") (pintype "bidirectional"))
    )
    (net (code "182") (name "unconnected-(OK1-A3-Pad5)") (class "Default")
      (node (ref "OK1") (pin "5") (pinfunction "A3_5") (pintype "bidirectional"))
    )
    (net (code "183") (name "unconnected-(OK1-A4-Pad7)") (class "Default")
      (node (ref "OK1") (pin "7") (pinfunction "A4_7") (pintype "bidirectional"))
    )
    (net (code "184") (name "unconnected-(OK1-C2-Pad14)") (class "Default")
      (node (ref "OK1") (pin "14") (pinfunction "C2_14") (pintype "bidirectional"))
    )
    (net (code "185") (name "unconnected-(OK1-C3-Pad12)") (class "Default")
      (node (ref "OK1") (pin "12") (pinfunction "C3_12") (pintype "bidirectional"))
    )
    (net (code "186") (name "unconnected-(OK1-C4-Pad10)") (class "Default")
      (node (ref "OK1") (pin "10") (pinfunction "C4_10") (pintype "bidirectional"))
    )
    (net (code "187") (name "unconnected-(OK1-E2-Pad13)") (class "Default")
      (node (ref "OK1") (pin "13") (pinfunction "E2_13") (pintype "bidirectional"))
    )
    (net (code "188") (name "unconnected-(OK1-E3-Pad11)") (class "Default")
      (node (ref "OK1") (pin "11") (pinfunction "E3_11") (pintype "bidirectional"))
    )
    (net (code "189") (name "unconnected-(OK1-E4-Pad9)") (class "Default")
      (node (ref "OK1") (pin "9") (pinfunction "E4_9") (pintype "bidirectional"))
    )
    (net (code "190") (name "unconnected-(OK1-K2-Pad4)") (class "Default")
      (node (ref "OK1") (pin "4") (pinfunction "K2_4") (pintype "bidirectional"))
    )
    (net (code "191") (name "unconnected-(OK1-K3-Pad6)") (class "Default")
      (node (ref "OK1") (pin "6") (pinfunction "K3_6") (pintype "bidirectional"))
    )
    (net (code "192") (name "unconnected-(OK1-K4-Pad8)") (class "Default")
      (node (ref "OK1") (pin "8") (pinfunction "K4_8") (pintype "bidirectional"))
    )
    (net (code "193") (name "unconnected-(U1-COMP-PadB7)") (class "Default")
      (node (ref "U1") (pin "B7") (pinfunction "COMP_B7") (pintype "bidirectional"))
    )
    (net (code "194") (name "unconnected-(U1-EXTV_CC-PadF6)") (class "Default")
      (node (ref "U1") (pin "F6") (pinfunction "EXTV_CC_F6") (pintype "bidirectional"))
    )
    (net (code "195") (name "unconnected-(U1-PLLIN-PadB9)") (class "Default")
      (node (ref "U1") (pin "B9") (pinfunction "PLLIN_B9") (pintype "bidirectional"))
    )
    (net (code "196") (name "unconnected-(U1-SS-PadA6)") (class "Default")
      (node (ref "U1") (pin "A6") (pinfunction "SS_A6") (pintype "bidirectional"))
    )
    (net (code "197") (name "unconnected-(U1-STBYMD-PadA10)") (class "Default")
      (node (ref "U1") (pin "A10") (pinfunction "STBYMD_A10") (pintype "bidirectional"))
    )
    (net (code "198") (name "unconnected-(U2-ADC_IN0-Pad2)") (class "Default")
      (node (ref "U2") (pin "2") (pinfunction "ADC_IN0_2") (pintype "bidirectional"))
    )
    (net (code "199") (name "unconnected-(U2-ADC_IN1-Pad1)") (class "Default")
      (node (ref "U2") (pin "1") (pinfunction "ADC_IN1_1") (pintype "bidirectional"))
    )
    (net (code "200") (name "unconnected-(U2-ADC_IN2-Pad4)") (class "Default")
      (node (ref "U2") (pin "4") (pinfunction "ADC_IN2_4") (pintype "bidirectional"))
    )
    (net (code "201") (name "unconnected-(U2-ADC_IN3-Pad3)") (class "Default")
      (node (ref "U2") (pin "3") (pinfunction "ADC_IN3_3") (pintype "bidirectional"))
    )
    (net (code "202") (name "unconnected-(U2-ADC_IN4-Pad6)") (class "Default")
      (node (ref "U2") (pin "6") (pinfunction "ADC_IN4_6") (pintype "bidirectional"))
    )
    (net (code "203") (name "unconnected-(U2-ADC_IN7-Pad5)") (class "Default")
      (node (ref "U2") (pin "5") (pinfunction "ADC_IN7_5") (pintype "bidirectional"))
    )
    (net (code "204") (name "unconnected-(U2-AGND-Pad8)") (class "Default")
      (node (ref "U2") (pin "8") (pinfunction "AGND_8") (pintype "bidirectional"))
    )
    (net (code "205") (name "unconnected-(U2-CAN1_RX-Pad20)") (class "Default")
      (node (ref "U2") (pin "20") (pinfunction "CAN1_RX_20") (pintype "bidirectional"))
    )
    (net (code "206") (name "unconnected-(U2-CAN1_TX-Pad22)") (class "Default")
      (node (ref "U2") (pin "22") (pinfunction "CAN1_TX_22") (pintype "bidirectional"))
    )
    (net (code "207") (name "unconnected-(U2-ERX_JM-Pad44)") (class "Default")
      (node (ref "U2") (pin "44") (pinfunction "ERX_JM_44") (pintype "bidirectional"))
    )
    (net (code "208") (name "unconnected-(U2-ERX_JP-Pad43)") (class "Default")
      (node (ref "U2") (pin "43") (pinfunction "ERX_JP_43") (pintype "bidirectional"))
    )
    (net (code "209") (name "unconnected-(U2-ETX_JM-Pad46)") (class "Default")
      (node (ref "U2") (pin "46") (pinfunction "ETX_JM_46") (pintype "bidirectional"))
    )
    (net (code "210") (name "unconnected-(U2-ETX_JP-Pad45)") (class "Default")
      (node (ref "U2") (pin "45") (pinfunction "ETX_JP_45") (pintype "bidirectional"))
    )
    (net (code "211") (name "unconnected-(U2-IRQ2-Pad50)") (class "Default")
      (node (ref "U2") (pin "50") (pinfunction "IRQ2_50") (pintype "bidirectional"))
    )
    (net (code "212") (name "unconnected-(U2-IRQ3-Pad49)") (class "Default")
      (node (ref "U2") (pin "49") (pinfunction "IRQ3_49") (pintype "bidirectional"))
    )
    (net (code "213") (name "unconnected-(U2-IRQ7-Pad9)") (class "Default")
      (node (ref "U2") (pin "9") (pinfunction "IRQ7_9") (pintype "bidirectional"))
    )
    (net (code "214") (name "unconnected-(U2-LINKLED-Pad42)") (class "Default")
      (node (ref "U2") (pin "42") (pinfunction "LINKLED_42") (pintype "bidirectional"))
    )
    (net (code "215") (name "unconnected-(U2-OW_DAT-Pad12)") (class "Default")
      (node (ref "U2") (pin "12") (pinfunction "OW_DAT_12") (pintype "bidirectional"))
    )
    (net (code "216") (name "unconnected-(U2-RSTI-Pad11)") (class "Default")
      (node (ref "U2") (pin "11") (pinfunction "RSTI_11") (pintype "bidirectional"))
    )
    (net (code "217") (name "unconnected-(U2-SDHC_DAT3-Pad15)") (class "Default")
      (node (ref "U2") (pin "15") (pinfunction "SDHC_DAT3_15") (pintype "bidirectional"))
    )
    (net (code "218") (name "unconnected-(U2-SPEEDLED-Pad40)") (class "Default")
      (node (ref "U2") (pin "40") (pinfunction "SPEEDLED_40") (pintype "bidirectional"))
    )
    (net (code "219") (name "unconnected-(U2-T0IN-Pad19)") (class "Default")
      (node (ref "U2") (pin "19") (pinfunction "T0IN_19") (pintype "bidirectional"))
    )
    (net (code "220") (name "unconnected-(U2-T1IN-Pad21)") (class "Default")
      (node (ref "U2") (pin "21") (pinfunction "T1IN_21") (pintype "bidirectional"))
    )
    (net (code "221") (name "unconnected-(U2-T3IN-Pad25)") (class "Default")
      (node (ref "U2") (pin "25") (pinfunction "T3IN_25") (pintype "bidirectional"))
    )
    (net (code "222") (name "unconnected-(U2-UART0_CTS-Pad30)") (class "Default")
      (node (ref "U2") (pin "30") (pinfunction "UART0_CTS_30") (pintype "bidirectional"))
    )
    (net (code "223") (name "unconnected-(U2-UART0_RTS-Pad28)") (class "Default")
      (node (ref "U2") (pin "28") (pinfunction "UART0_RTS_28") (pintype "bidirectional"))
    )
    (net (code "224") (name "unconnected-(U2-UART0_RX-Pad24)") (class "Default")
      (node (ref "U2") (pin "24") (pinfunction "UART0_RX_24") (pintype "bidirectional"))
    )
    (net (code "225") (name "unconnected-(U2-UART0_TX-Pad26)") (class "Default")
      (node (ref "U2") (pin "26") (pinfunction "UART0_TX_26") (pintype "bidirectional"))
    )
    (net (code "226") (name "unconnected-(U2-UART2_CTS-Pad10)") (class "Default")
      (node (ref "U2") (pin "10") (pinfunction "UART2_CTS_10") (pintype "bidirectional"))
    )
    (net (code "227") (name "unconnected-(U2-UART2_RTS-Pad14)") (class "Default")
      (node (ref "U2") (pin "14") (pinfunction "UART2_RTS_14") (pintype "bidirectional"))
    )
    (net (code "228") (name "unconnected-(U2-UART2_RX-Pad13)") (class "Default")
      (node (ref "U2") (pin "13") (pinfunction "UART2_RX_13") (pintype "bidirectional"))
    )
    (net (code "229") (name "unconnected-(U2-UART2_TX-Pad16)") (class "Default")
      (node (ref "U2") (pin "16") (pinfunction "UART2_TX_16") (pintype "bidirectional"))
    )
    (net (code "230") (name "unconnected-(U2-USBO_DM-Pad51)") (class "Default")
      (node (ref "U2") (pin "51") (pinfunction "USBO_DM_51") (pintype "bidirectional"))
    )
    (net (code "231") (name "unconnected-(U2-USBO_DP-Pad52)") (class "Default")
      (node (ref "U2") (pin "52") (pinfunction "USBO_DP_52") (pintype "bidirectional"))
    )
    (net (code "232") (name "unconnected-(U2-VCC3VE-Pad41)") (class "Default")
      (node (ref "U2") (pin "41") (pinfunction "VCC3VE_41") (pintype "bidirectional"))
    )
    (net (code "233") (name "unconnected-(U2-VDDA_DAC_ADC-Pad7)") (class "Default")
      (node (ref "U2") (pin "7") (pinfunction "VDDA_DAC_ADC_7") (pintype "bidirectional"))
    )
    (net (code "234") (name "unconnected-(U3-TIMER1-Pad2)") (class "Default")
      (node (ref "U3") (pin "2") (pinfunction "TIMER1_2") (pintype "bidirectional"))
    )
    (net (code "235") (name "unconnected-(U3-TIMER2-Pad4)") (class "Default")
      (node (ref "U3") (pin "4") (pinfunction "TIMER2_4") (pintype "bidirectional"))
    )
    (net (code "236") (name "unconnected-(U3-TIMER3-Pad6)") (class "Default")
      (node (ref "U3") (pin "6") (pinfunction "TIMER3_6") (pintype "bidirectional"))
    )
    (net (code "237") (name "unconnected-(U3-TIMER4-Pad8)") (class "Default")
      (node (ref "U3") (pin "8") (pinfunction "TIMER4_8") (pintype "bidirectional"))
    )
    (net (code "238") (name "unconnected-(U4-TIMER1-Pad2)") (class "Default")
      (node (ref "U4") (pin "2") (pinfunction "TIMER1_2") (pintype "bidirectional"))
    )
    (net (code "239") (name "unconnected-(U4-TIMER2-Pad4)") (class "Default")
      (node (ref "U4") (pin "4") (pinfunction "TIMER2_4") (pintype "bidirectional"))
    )
    (net (code "240") (name "unconnected-(U4-TIMER3-Pad6)") (class "Default")
      (node (ref "U4") (pin "6") (pinfunction "TIMER3_6") (pintype "bidirectional"))
    )
    (net (code "241") (name "unconnected-(U4-TIMER4-Pad8)") (class "Default")
      (node (ref "U4") (pin "8") (pinfunction "TIMER4_8") (pintype "bidirectional"))
    )
  )
)
